# AFE.net
KiCad netlist of a schematic drawn in Altium Designer
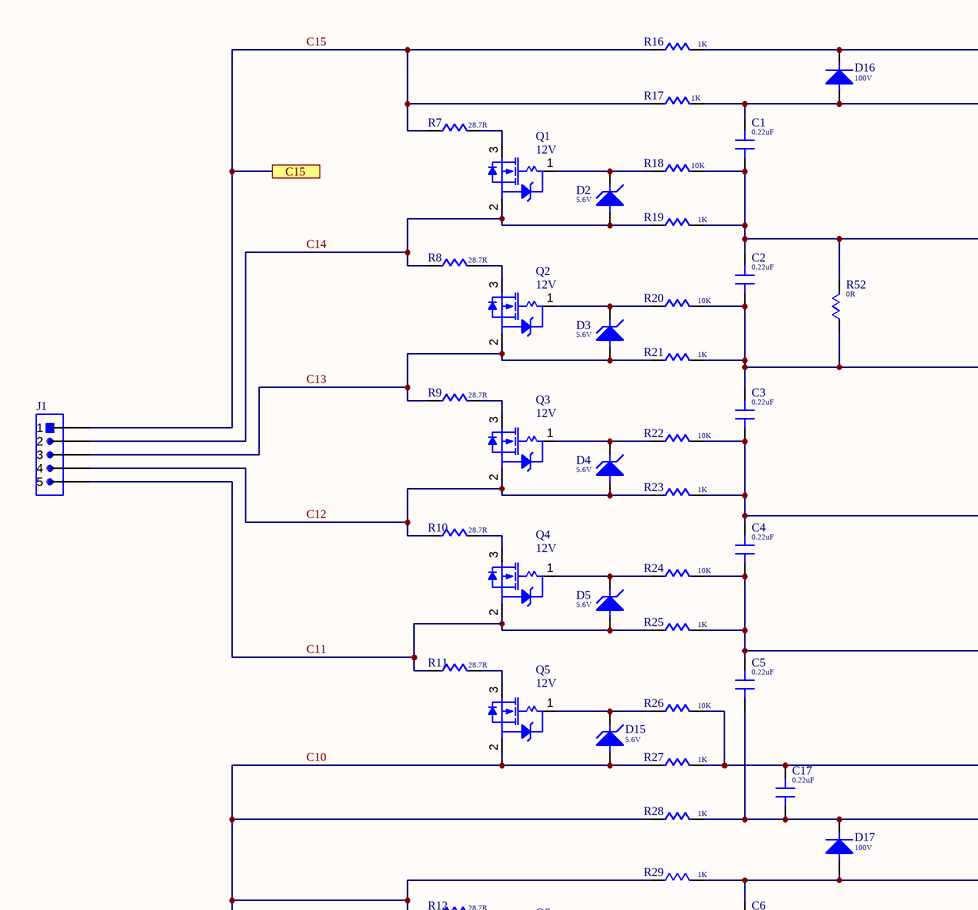
[diagram p0: AFE.SchDoc, top left]
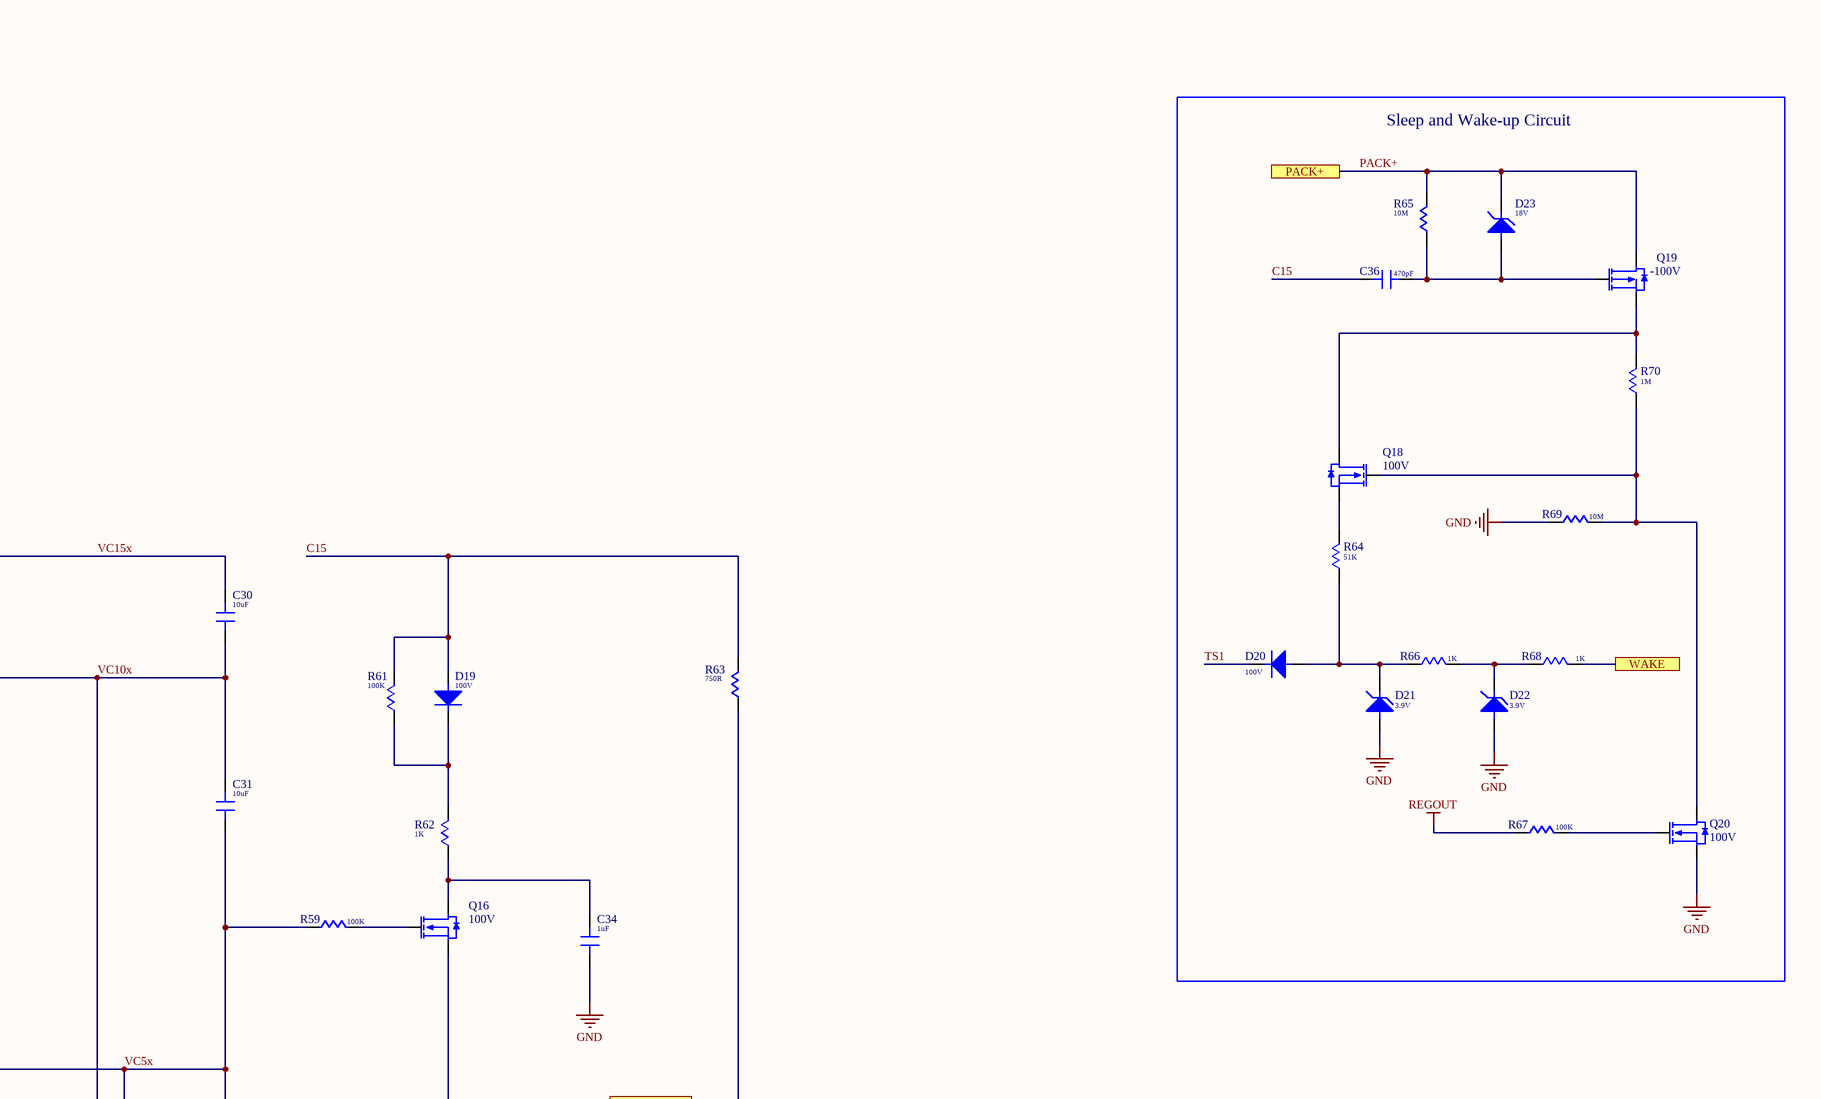
[diagram p1: AFE.SchDoc, top right]
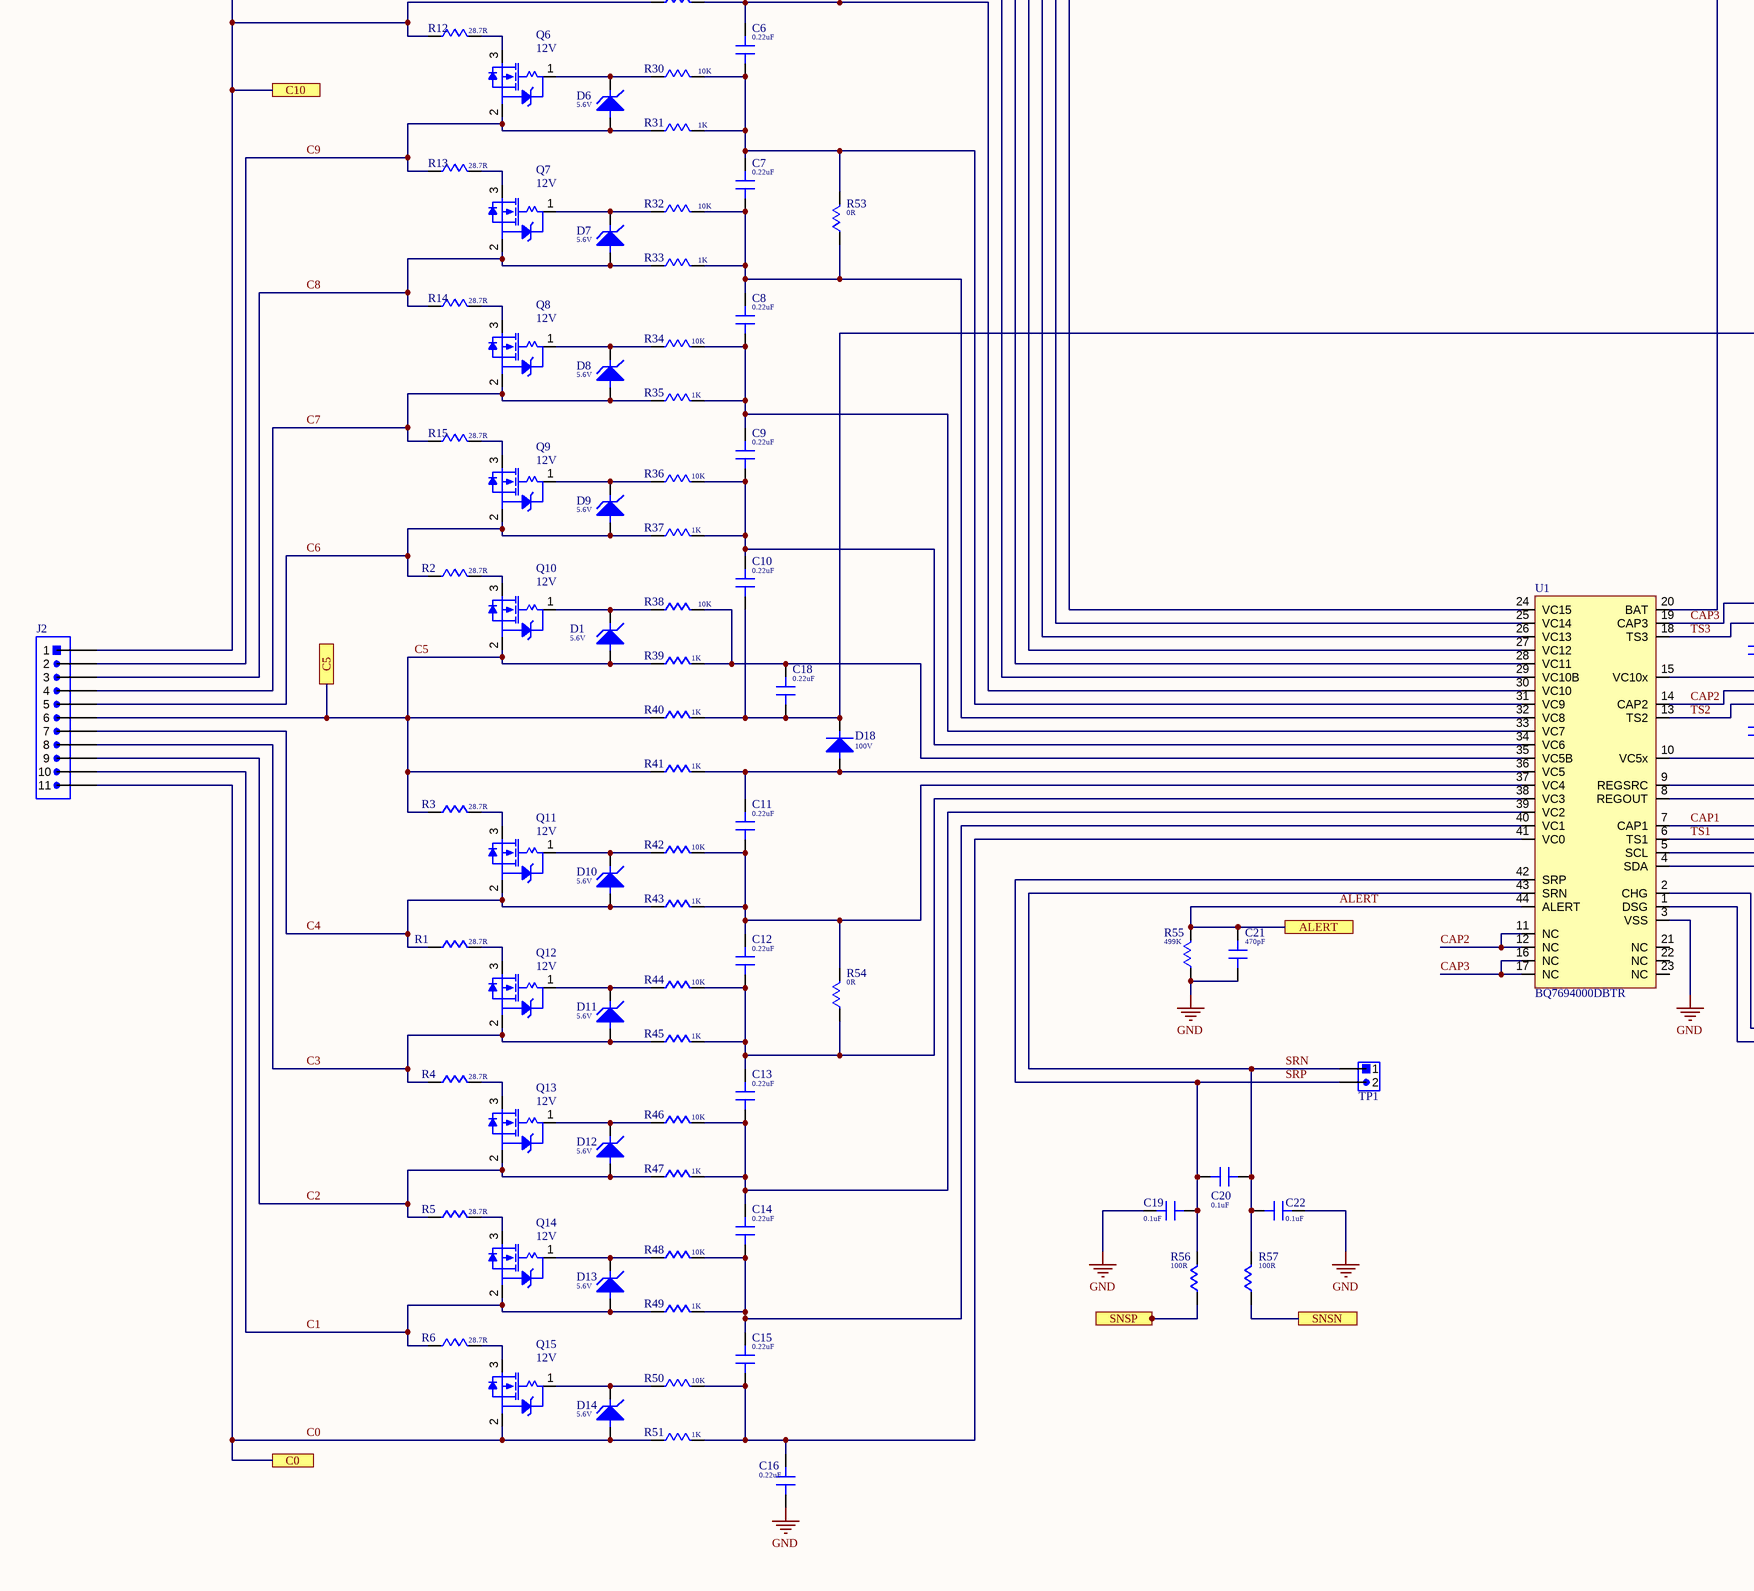
[diagram p2: AFE.SchDoc, bottom left]
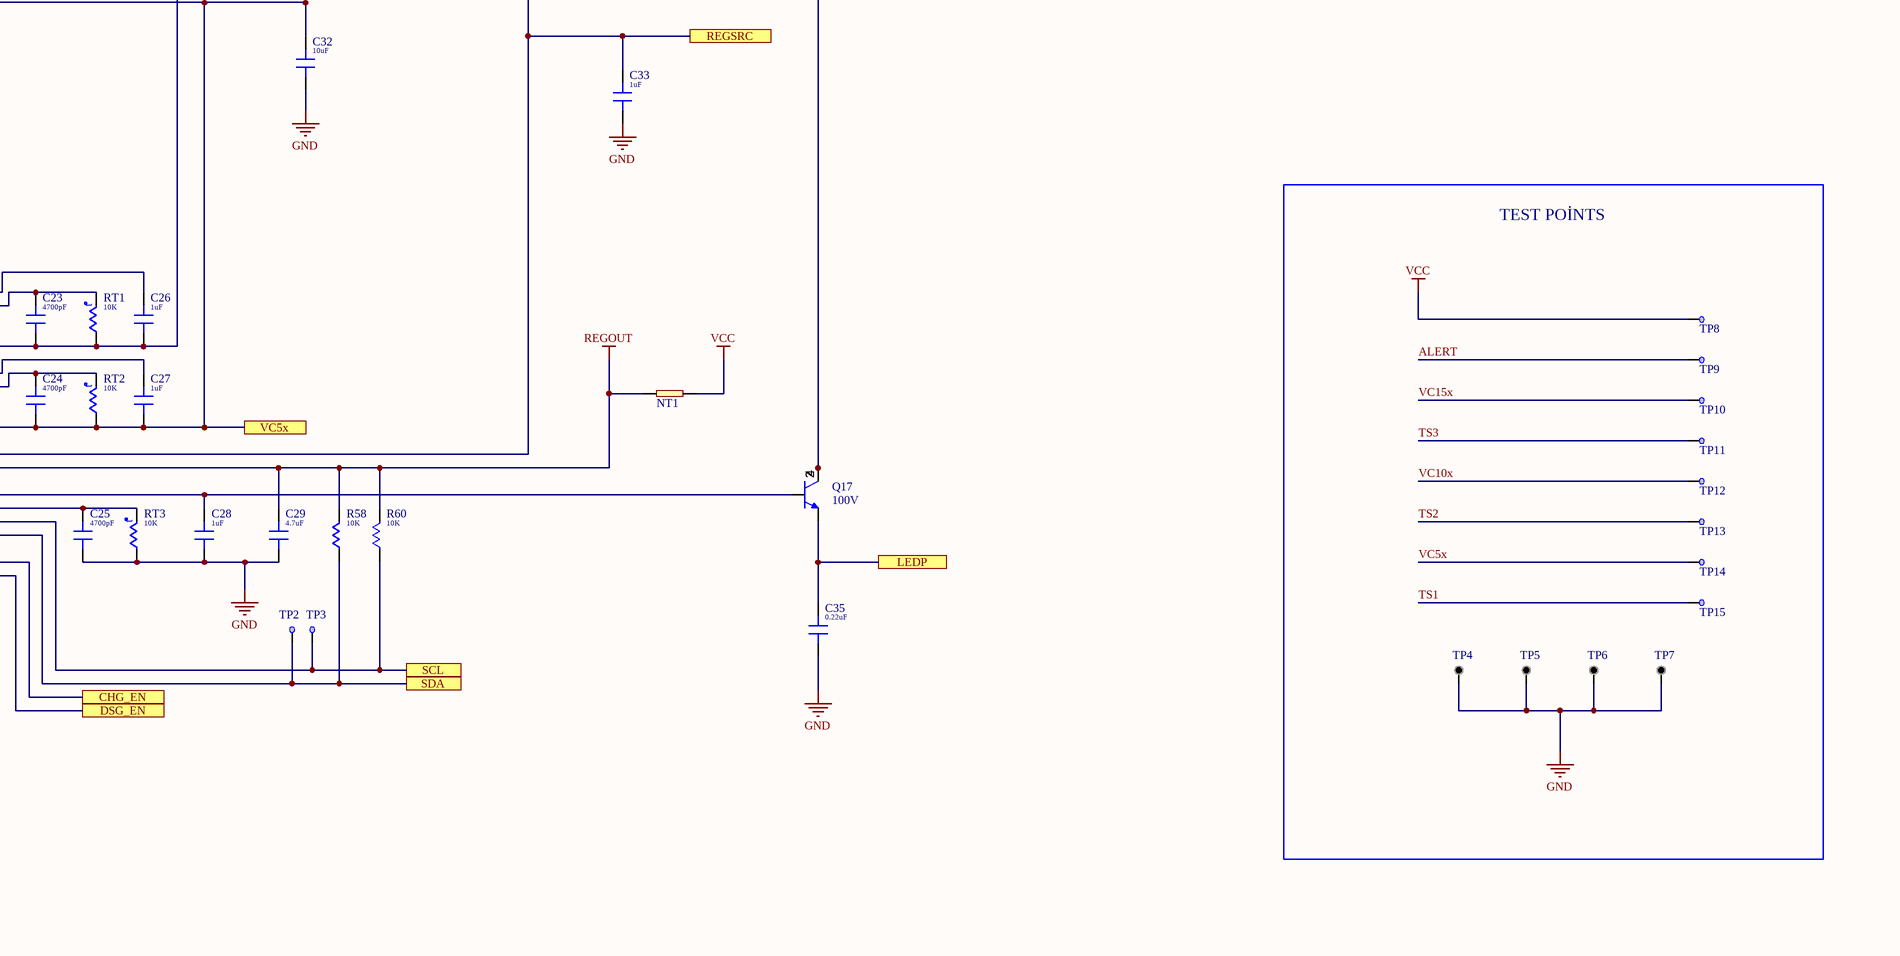
[diagram p3: AFE.SchDoc, bottom right]

(export (version "E")
  (design (tool "Eeschema 10.0.6"))
  (components
    (comp (ref "C1")
      (value "0.22uF")
      (footprint "C_0603")
      (description "Ceramic Capacitor 220nF, 16VDC, 0603, ±10 %")
      (fields
        (field (name "MANUFACTURER") "Wurth Electronics")
        (field (name "MANUFACTURER PART NUMBER") "885012206048")
      )
      (libsource (lib "BMS_Lib") (part "C_0.22uF_0603_16V"))
    )
    (comp (ref "C2")
      (value "0.22uF")
      (footprint "C_0603")
      (description "Ceramic Capacitor 220nF, 16VDC, 0603, ±10 %")
      (fields
        (field (name "MANUFACTURER") "Wurth Electronics")
        (field (name "MANUFACTURER PART NUMBER") "885012206048")
      )
      (libsource (lib "BMS_Lib") (part "C_0.22uF_0603_16V"))
    )
    (comp (ref "C3")
      (value "0.22uF")
      (footprint "C_0603")
      (description "Ceramic Capacitor 220nF, 16VDC, 0603, ±10 %")
      (fields
        (field (name "MANUFACTURER") "Wurth Electronics")
        (field (name "MANUFACTURER PART NUMBER") "885012206048")
      )
      (libsource (lib "BMS_Lib") (part "C_0.22uF_0603_16V"))
    )
    (comp (ref "C4")
      (value "0.22uF")
      (footprint "C_0603")
      (description "Ceramic Capacitor 220nF, 16VDC, 0603, ±10 %")
      (fields
        (field (name "MANUFACTURER") "Wurth Electronics")
        (field (name "MANUFACTURER PART NUMBER") "885012206048")
      )
      (libsource (lib "BMS_Lib") (part "C_0.22uF_0603_16V"))
    )
    (comp (ref "C5")
      (value "0.22uF")
      (footprint "C_0603")
      (description "Ceramic Capacitor 220nF, 16VDC, 0603, ±10 %")
      (fields
        (field (name "MANUFACTURER") "Wurth Electronics")
        (field (name "MANUFACTURER PART NUMBER") "885012206048")
      )
      (libsource (lib "BMS_Lib") (part "C_0.22uF_0603_16V"))
    )
    (comp (ref "C6")
      (value "0.22uF")
      (footprint "C_0603")
      (description "Ceramic Capacitor 220nF, 16VDC, 0603, ±10 %")
      (fields
        (field (name "MANUFACTURER") "Wurth Electronics")
        (field (name "MANUFACTURER PART NUMBER") "885012206048")
      )
      (libsource (lib "BMS_Lib") (part "C_0.22uF_0603_16V"))
    )
    (comp (ref "C7")
      (value "0.22uF")
      (footprint "C_0603")
      (description "Ceramic Capacitor 220nF, 16VDC, 0603, ±10 %")
      (fields
        (field (name "MANUFACTURER") "Wurth Electronics")
        (field (name "MANUFACTURER PART NUMBER") "885012206048")
      )
      (libsource (lib "BMS_Lib") (part "C_0.22uF_0603_16V"))
    )
    (comp (ref "C8")
      (value "0.22uF")
      (footprint "C_0603")
      (description "Ceramic Capacitor 220nF, 16VDC, 0603, ±10 %")
      (fields
        (field (name "MANUFACTURER") "Wurth Electronics")
        (field (name "MANUFACTURER PART NUMBER") "885012206048")
      )
      (libsource (lib "BMS_Lib") (part "C_0.22uF_0603_16V"))
    )
    (comp (ref "C9")
      (value "0.22uF")
      (footprint "C_0603")
      (description "Ceramic Capacitor 220nF, 16VDC, 0603, ±10 %")
      (fields
        (field (name "MANUFACTURER") "Wurth Electronics")
        (field (name "MANUFACTURER PART NUMBER") "885012206048")
      )
      (libsource (lib "BMS_Lib") (part "C_0.22uF_0603_16V"))
    )
    (comp (ref "C10")
      (value "0.22uF")
      (footprint "C_0603")
      (description "Ceramic Capacitor 220nF, 16VDC, 0603, ±10 %")
      (fields
        (field (name "MANUFACTURER") "Wurth Electronics")
        (field (name "MANUFACTURER PART NUMBER") "885012206048")
      )
      (libsource (lib "BMS_Lib") (part "C_0.22uF_0603_16V"))
    )
    (comp (ref "C11")
      (value "0.22uF")
      (footprint "C_0603")
      (description "Ceramic Capacitor 220nF, 16VDC, 0603, ±10 %")
      (fields
        (field (name "MANUFACTURER") "Wurth Electronics")
        (field (name "MANUFACTURER PART NUMBER") "885012206048")
      )
      (libsource (lib "BMS_Lib") (part "C_0.22uF_0603_16V"))
    )
    (comp (ref "C12")
      (value "0.22uF")
      (footprint "C_0603")
      (description "Ceramic Capacitor 220nF, 16VDC, 0603, ±10 %")
      (fields
        (field (name "MANUFACTURER") "Wurth Electronics")
        (field (name "MANUFACTURER PART NUMBER") "885012206048")
      )
      (libsource (lib "BMS_Lib") (part "C_0.22uF_0603_16V"))
    )
    (comp (ref "C13")
      (value "0.22uF")
      (footprint "C_0603")
      (description "Ceramic Capacitor 220nF, 16VDC, 0603, ±10 %")
      (fields
        (field (name "MANUFACTURER") "Wurth Electronics")
        (field (name "MANUFACTURER PART NUMBER") "885012206048")
      )
      (libsource (lib "BMS_Lib") (part "C_0.22uF_0603_16V"))
    )
    (comp (ref "C14")
      (value "0.22uF")
      (footprint "C_0603")
      (description "Ceramic Capacitor 220nF, 16VDC, 0603, ±10 %")
      (fields
        (field (name "MANUFACTURER") "Wurth Electronics")
        (field (name "MANUFACTURER PART NUMBER") "885012206048")
      )
      (libsource (lib "BMS_Lib") (part "C_0.22uF_0603_16V"))
    )
    (comp (ref "C15")
      (value "0.22uF")
      (footprint "C_0603")
      (description "Ceramic Capacitor 220nF, 16VDC, 0603, ±10 %")
      (fields
        (field (name "MANUFACTURER") "Wurth Electronics")
        (field (name "MANUFACTURER PART NUMBER") "885012206048")
      )
      (libsource (lib "BMS_Lib") (part "C_0.22uF_0603_16V"))
    )
    (comp (ref "C16")
      (value "0.22uF")
      (footprint "C_0603")
      (description "Ceramic Capacitor 220nF, 16VDC, 0603, ±10 %")
      (fields
        (field (name "MANUFACTURER") "Wurth Electronics")
        (field (name "MANUFACTURER PART NUMBER") "885012206048")
      )
      (libsource (lib "BMS_Lib") (part "C_0.22uF_0603_16V"))
    )
    (comp (ref "C17")
      (value "0.22uF")
      (footprint "C_0603")
      (description "Ceramic Capacitor 220nF, 16VDC, 0603, ±10 %")
      (fields
        (field (name "MANUFACTURER") "Wurth Electronics")
        (field (name "MANUFACTURER PART NUMBER") "885012206048")
      )
      (libsource (lib "BMS_Lib") (part "C_0.22uF_0603_16V"))
    )
    (comp (ref "C18")
      (value "0.22uF")
      (footprint "C_0603")
      (description "Ceramic Capacitor 220nF, 16VDC, 0603, ±10 %")
      (fields
        (field (name "MANUFACTURER") "Wurth Electronics")
        (field (name "MANUFACTURER PART NUMBER") "885012206048")
      )
      (libsource (lib "BMS_Lib") (part "C_0.22uF_0603_16V"))
    )
    (comp (ref "C19")
      (value "0.1uF")
      (footprint "C_0603")
      (description "Ceramic Capacitor, Multilayer, Ceramic, 50V, 10% -Tol, X7R, 15% Tc, 0.1Uf, Surface Mount, 0603")
      (fields
        (field (name "MANUFACTURER") "TDK")
        (field (name "MANUFACTURER PART NUMBER") "C1608X7R1H104K080AA")
      )
      (libsource (lib "BMS_Lib") (part "C_0.1uF_0603_50V"))
    )
    (comp (ref "C20")
      (value "0.1uF")
      (footprint "C_0603")
      (description "Ceramic Capacitor, Multilayer, Ceramic, 50V, 10% -Tol, X7R, 15% Tc, 0.1Uf, Surface Mount, 0603")
      (fields
        (field (name "MANUFACTURER") "TDK")
        (field (name "MANUFACTURER PART NUMBER") "C1608X7R1H104K080AA")
      )
      (libsource (lib "BMS_Lib") (part "C_0.1uF_0603_50V"))
    )
    (comp (ref "C21")
      (value "470pF")
      (footprint "C_0603")
      (description "WCAP-CSGP 0603 (1608Metric) Ceramic Capacitor 0.063Lx0.031W 1.60mmx0.80mm X7R ±10% 470pF")
      (fields
        (field (name "MANUFACTURER") "Wurth Electronics")
        (field (name "MANUFACTURER PART NUMBER") "885012206081")
      )
      (libsource (lib "BMS_Lib") (part "C_470pF_0603_50V"))
    )
    (comp (ref "C22")
      (value "0.1uF")
      (footprint "C_0603")
      (description "Ceramic Capacitor, Multilayer, Ceramic, 50V, 10% -Tol, X7R, 15% Tc, 0.1Uf, Surface Mount, 0603")
      (fields
        (field (name "MANUFACTURER") "TDK")
        (field (name "MANUFACTURER PART NUMBER") "C1608X7R1H104K080AA")
      )
      (libsource (lib "BMS_Lib") (part "C_0.1uF_0603_50V"))
    )
    (comp (ref "C23")
      (value "4700pF")
      (footprint "C_0603")
      (description "Cap Cer 4700PF 50V X7R 0603")
      (fields
        (field (name "MANUFACTURER") "Wurth Electronics")
        (field (name "MANUFACTURER PART NUMBER") "885012206087")
      )
      (libsource (lib "BMS_Lib") (part "C_4700pF_0603_50V"))
    )
    (comp (ref "C24")
      (value "4700pF")
      (footprint "C_0603")
      (description "Cap Cer 4700PF 50V X7R 0603")
      (fields
        (field (name "MANUFACTURER") "Wurth Electronics")
        (field (name "MANUFACTURER PART NUMBER") "885012206087")
      )
      (libsource (lib "BMS_Lib") (part "C_4700pF_0603_50V"))
    )
    (comp (ref "C25")
      (value "4700pF")
      (footprint "C_0603")
      (description "Cap Cer 4700PF 50V X7R 0603")
      (fields
        (field (name "MANUFACTURER") "Wurth Electronics")
        (field (name "MANUFACTURER PART NUMBER") "885012206087")
      )
      (libsource (lib "BMS_Lib") (part "C_4700pF_0603_50V"))
    )
    (comp (ref "C26")
      (value "1uF")
      (footprint "C_0603")
      (fields
        (field (name "MANUFACTURER") "Wurth Electronics")
        (field (name "MANUFACTURER PART NUMBER") "885012206052")
        (field (name "TOLERANCE") "10%")
      )
      (libsource (lib "BMS_Lib") (part "C_1uF_0603_16V"))
    )
    (comp (ref "C27")
      (value "1uF")
      (footprint "C_0603")
      (fields
        (field (name "MANUFACTURER") "Wurth Electronics")
        (field (name "MANUFACTURER PART NUMBER") "885012206052")
        (field (name "TOLERANCE") "10%")
      )
      (libsource (lib "BMS_Lib") (part "C_1uF_0603_16V"))
    )
    (comp (ref "C28")
      (value "1uF")
      (footprint "C_0603")
      (fields
        (field (name "MANUFACTURER") "Wurth Electronics")
        (field (name "MANUFACTURER PART NUMBER") "885012206052")
        (field (name "TOLERANCE") "10%")
      )
      (libsource (lib "BMS_Lib") (part "C_1uF_0603_16V"))
    )
    (comp (ref "C29")
      (value "4.7uF")
      (footprint "C_0805")
      (fields
        (field (name "MANUFACTURER") "Wurth Electronics")
        (field (name "MANUFACTURER PART NUMBER") "885012207025")
      )
      (libsource (lib "BMS_Lib") (part "C_4.7uF_0805_10V"))
    )
    (comp (ref "C30")
      (value "10uF")
      (footprint "C_1210")
      (description "Multilayer Ceramic Capacitor, 10 uF, 35 V, ± 10%, X7R, 1210 [3225 Metric]")
      (fields
        (field (name "MANUFACTURER") "Murata")
        (field (name "MANUFACTURER PART NUMBER") "GRM32ER7YA106KA12L")
      )
      (libsource (lib "BMS_Lib") (part "C_10uF_1210_35V"))
    )
    (comp (ref "C31")
      (value "10uF")
      (footprint "C_1210")
      (description "Multilayer Ceramic Capacitor, 10 uF, 35 V, ± 10%, X7R, 1210 [3225 Metric]")
      (fields
        (field (name "MANUFACTURER") "Murata")
        (field (name "MANUFACTURER PART NUMBER") "GRM32ER7YA106KA12L")
      )
      (libsource (lib "BMS_Lib") (part "C_10uF_1210_35V"))
    )
    (comp (ref "C32")
      (value "10uF")
      (footprint "C_1210")
      (description "Multilayer Ceramic Capacitor, 10 uF, 35 V, ± 10%, X7R, 1210 [3225 Metric]")
      (fields
        (field (name "MANUFACTURER") "Murata")
        (field (name "MANUFACTURER PART NUMBER") "GRM32ER7YA106KA12L")
      )
      (libsource (lib "BMS_Lib") (part "C_10uF_1210_35V"))
    )
    (comp (ref "C33")
      (value "1uF")
      (footprint "C_0805")
      (description "CAP CER 1UF 50V X7R 0805")
      (fields (field (name "TOLERANCE") "+-10%") (field (name "Comment") "GRM21BR71H105KA12L"))
      (libsource (lib "BMS_Lib") (part "C_1uF_0805_50V"))
    )
    (comp (ref "C34")
      (value "1uF")
      (footprint "C_0805")
      (description "CAP CER 1UF 50V X7R 0805")
      (fields (field (name "TOLERANCE") "+-10%") (field (name "Comment") "GRM21BR71H105KA12L"))
      (libsource (lib "BMS_Lib") (part "C_1uF_0805_50V"))
    )
    (comp (ref "C35")
      (value "0.22uF")
      (footprint "C_0603")
      (description "Ceramic Capacitor 220nF, 16VDC, 0603, ±10 %")
      (fields
        (field (name "MANUFACTURER") "Wurth Electronics")
        (field (name "MANUFACTURER PART NUMBER") "885012206048")
      )
      (libsource (lib "BMS_Lib") (part "C_0.22uF_0603_16V"))
    )
    (comp (ref "C36")
      (value "470pF")
      (footprint "C_0603")
      (description "WCAP-CSGP 0603 (1608Metric) Ceramic Capacitor 0.063Lx0.031W 1.60mmx0.80mm X7R ±10% 470pF")
      (fields
        (field (name "MANUFACTURER") "Wurth Electronics")
        (field (name "MANUFACTURER PART NUMBER") "885012206081")
      )
      (libsource (lib "BMS_Lib") (part "C_470pF_0603_50V"))
    )
    (comp (ref "D1")
      (value "5.6V")
      (footprint "D_SOD323")
      (description "Diode Zener Single 5.6V 5% 200mW Automotive 2-Pin SOD-323 T/R")
      (fields
        (field (name "MANUFACTURER") "Diodes")
        (field (name "MANUFACTURER PART NUMBER") "MMSZ5232BS-7-F")
      )
      (libsource (lib "BMS_Lib") (part "D_ZENER_5.6V_SOD323"))
    )
    (comp (ref "D2")
      (value "5.6V")
      (footprint "D_SOD323")
      (description "Diode Zener Single 5.6V 5% 200mW Automotive 2-Pin SOD-323 T/R")
      (fields
        (field (name "MANUFACTURER") "Diodes")
        (field (name "MANUFACTURER PART NUMBER") "MMSZ5232BS-7-F")
      )
      (libsource (lib "BMS_Lib") (part "D_ZENER_5.6V_SOD323"))
    )
    (comp (ref "D3")
      (value "5.6V")
      (footprint "D_SOD323")
      (description "Diode Zener Single 5.6V 5% 200mW Automotive 2-Pin SOD-323 T/R")
      (fields
        (field (name "MANUFACTURER") "Diodes")
        (field (name "MANUFACTURER PART NUMBER") "MMSZ5232BS-7-F")
      )
      (libsource (lib "BMS_Lib") (part "D_ZENER_5.6V_SOD323"))
    )
    (comp (ref "D4")
      (value "5.6V")
      (footprint "D_SOD323")
      (description "Diode Zener Single 5.6V 5% 200mW Automotive 2-Pin SOD-323 T/R")
      (fields
        (field (name "MANUFACTURER") "Diodes")
        (field (name "MANUFACTURER PART NUMBER") "MMSZ5232BS-7-F")
      )
      (libsource (lib "BMS_Lib") (part "D_ZENER_5.6V_SOD323"))
    )
    (comp (ref "D5")
      (value "5.6V")
      (footprint "D_SOD323")
      (description "Diode Zener Single 5.6V 5% 200mW Automotive 2-Pin SOD-323 T/R")
      (fields
        (field (name "MANUFACTURER") "Diodes")
        (field (name "MANUFACTURER PART NUMBER") "MMSZ5232BS-7-F")
      )
      (libsource (lib "BMS_Lib") (part "D_ZENER_5.6V_SOD323"))
    )
    (comp (ref "D6")
      (value "5.6V")
      (footprint "D_SOD323")
      (description "Diode Zener Single 5.6V 5% 200mW Automotive 2-Pin SOD-323 T/R")
      (fields
        (field (name "MANUFACTURER") "Diodes")
        (field (name "MANUFACTURER PART NUMBER") "MMSZ5232BS-7-F")
      )
      (libsource (lib "BMS_Lib") (part "D_ZENER_5.6V_SOD323"))
    )
    (comp (ref "D7")
      (value "5.6V")
      (footprint "D_SOD323")
      (description "Diode Zener Single 5.6V 5% 200mW Automotive 2-Pin SOD-323 T/R")
      (fields
        (field (name "MANUFACTURER") "Diodes")
        (field (name "MANUFACTURER PART NUMBER") "MMSZ5232BS-7-F")
      )
      (libsource (lib "BMS_Lib") (part "D_ZENER_5.6V_SOD323"))
    )
    (comp (ref "D8")
      (value "5.6V")
      (footprint "D_SOD323")
      (description "Diode Zener Single 5.6V 5% 200mW Automotive 2-Pin SOD-323 T/R")
      (fields
        (field (name "MANUFACTURER") "Diodes")
        (field (name "MANUFACTURER PART NUMBER") "MMSZ5232BS-7-F")
      )
      (libsource (lib "BMS_Lib") (part "D_ZENER_5.6V_SOD323"))
    )
    (comp (ref "D9")
      (value "5.6V")
      (footprint "D_SOD323")
      (description "Diode Zener Single 5.6V 5% 200mW Automotive 2-Pin SOD-323 T/R")
      (fields
        (field (name "MANUFACTURER") "Diodes")
        (field (name "MANUFACTURER PART NUMBER") "MMSZ5232BS-7-F")
      )
      (libsource (lib "BMS_Lib") (part "D_ZENER_5.6V_SOD323"))
    )
    (comp (ref "D10")
      (value "5.6V")
      (footprint "D_SOD323")
      (description "Diode Zener Single 5.6V 5% 200mW Automotive 2-Pin SOD-323 T/R")
      (fields
        (field (name "MANUFACTURER") "Diodes")
        (field (name "MANUFACTURER PART NUMBER") "MMSZ5232BS-7-F")
      )
      (libsource (lib "BMS_Lib") (part "D_ZENER_5.6V_SOD323"))
    )
    (comp (ref "D11")
      (value "5.6V")
      (footprint "D_SOD323")
      (description "Diode Zener Single 5.6V 5% 200mW Automotive 2-Pin SOD-323 T/R")
      (fields
        (field (name "MANUFACTURER") "Diodes")
        (field (name "MANUFACTURER PART NUMBER") "MMSZ5232BS-7-F")
      )
      (libsource (lib "BMS_Lib") (part "D_ZENER_5.6V_SOD323"))
    )
    (comp (ref "D12")
      (value "5.6V")
      (footprint "D_SOD323")
      (description "Diode Zener Single 5.6V 5% 200mW Automotive 2-Pin SOD-323 T/R")
      (fields
        (field (name "MANUFACTURER") "Diodes")
        (field (name "MANUFACTURER PART NUMBER") "MMSZ5232BS-7-F")
      )
      (libsource (lib "BMS_Lib") (part "D_ZENER_5.6V_SOD323"))
    )
    (comp (ref "D13")
      (value "5.6V")
      (footprint "D_SOD323")
      (description "Diode Zener Single 5.6V 5% 200mW Automotive 2-Pin SOD-323 T/R")
      (fields
        (field (name "MANUFACTURER") "Diodes")
        (field (name "MANUFACTURER PART NUMBER") "MMSZ5232BS-7-F")
      )
      (libsource (lib "BMS_Lib") (part "D_ZENER_5.6V_SOD323"))
    )
    (comp (ref "D14")
      (value "5.6V")
      (footprint "D_SOD323")
      (description "Diode Zener Single 5.6V 5% 200mW Automotive 2-Pin SOD-323 T/R")
      (fields
        (field (name "MANUFACTURER") "Diodes")
        (field (name "MANUFACTURER PART NUMBER") "MMSZ5232BS-7-F")
      )
      (libsource (lib "BMS_Lib") (part "D_ZENER_5.6V_SOD323"))
    )
    (comp (ref "D15")
      (value "5.6V")
      (footprint "D_SOD323")
      (description "Diode Zener Single 5.6V 5% 200mW Automotive 2-Pin SOD-323 T/R")
      (fields
        (field (name "MANUFACTURER") "Diodes")
        (field (name "MANUFACTURER PART NUMBER") "MMSZ5232BS-7-F")
      )
      (libsource (lib "BMS_Lib") (part "D_ZENER_5.6V_SOD323"))
    )
    (comp (ref "D16")
      (value "100V")
      (footprint "D_SOD123")
      (description "Small Signal Diode, Single, 100 V, 300 mA, 1.25 V, 4 ns, 2 A RoHS Compliant: Yes")
      (fields (field (name "MANUFACTURER") "Diodes") (field (name "MANUFACTURER PART NUMBER") "1N4148W-7-F"))
      (libsource (lib "BMS_Lib") (part "D_GENPURP_100V_SOD123"))
    )
    (comp (ref "D17")
      (value "100V")
      (footprint "D_SOD123")
      (description "Small Signal Diode, Single, 100 V, 300 mA, 1.25 V, 4 ns, 2 A RoHS Compliant: Yes")
      (fields (field (name "MANUFACTURER") "Diodes") (field (name "MANUFACTURER PART NUMBER") "1N4148W-7-F"))
      (libsource (lib "BMS_Lib") (part "D_GENPURP_100V_SOD123"))
    )
    (comp (ref "D18")
      (value "100V")
      (footprint "D_SOD123")
      (description "Small Signal Diode, Single, 100 V, 300 mA, 1.25 V, 4 ns, 2 A RoHS Compliant: Yes")
      (fields (field (name "MANUFACTURER") "Diodes") (field (name "MANUFACTURER PART NUMBER") "1N4148W-7-F"))
      (libsource (lib "BMS_Lib") (part "D_GENPURP_100V_SOD123"))
    )
    (comp (ref "D19")
      (value "100V")
      (footprint "D_SOD123")
      (description "Small Signal Diode, Single, 100 V, 300 mA, 1.25 V, 4 ns, 2 A RoHS Compliant: Yes")
      (fields (field (name "MANUFACTURER") "Diodes") (field (name "MANUFACTURER PART NUMBER") "1N4148W-7-F"))
      (libsource (lib "BMS_Lib") (part "D_GENPURP_100V_SOD123"))
    )
    (comp (ref "D20")
      (value "100V")
      (footprint "D_SOD123")
      (description "Small Signal Diode, Single, 100 V, 300 mA, 1.25 V, 4 ns, 2 A RoHS Compliant: Yes")
      (fields (field (name "MANUFACTURER") "Diodes") (field (name "MANUFACTURER PART NUMBER") "1N4148W-7-F"))
      (libsource (lib "BMS_Lib") (part "D_GENPURP_100V_SOD123"))
    )
    (comp (ref "D21")
      (value "3.9V")
      (footprint "D_SOD323")
      (description "MMSZ5228BS Series 3.9 V 10 mA 200 mW Surface Mount Zener Diode - SOD-323")
      (fields
        (field (name "MANUFACTURER") "Diodes")
        (field (name "MANUFACTURER PART NUMBER") "MMSZ5228BS-7-F")
      )
      (libsource (lib "BMS_Lib") (part "D_ZENER_3.9V_SOD323"))
    )
    (comp (ref "D22")
      (value "3.9V")
      (footprint "D_SOD323")
      (description "MMSZ5228BS Series 3.9 V 10 mA 200 mW Surface Mount Zener Diode - SOD-323")
      (fields
        (field (name "MANUFACTURER") "Diodes")
        (field (name "MANUFACTURER PART NUMBER") "MMSZ5228BS-7-F")
      )
      (libsource (lib "BMS_Lib") (part "D_ZENER_3.9V_SOD323"))
    )
    (comp (ref "D23")
      (value "18V")
      (footprint "D_SOD323")
      (description "Diode Zener Single 18V 5% 200mW Automotive 2-Pin SOD-323 T/R")
      (fields
        (field (name "MANUFACTURER") "Diodes")
        (field (name "MANUFACTURER PART NUMBER") "MMSZ5248BS-7-F")
      )
      (libsource (lib "BMS_Lib") (part "D_ZENER_18V_SOD323"))
    )
    (comp (ref "J1")
      (value "0395021005")
      (footprint "TB_5")
      (description "Conn Shrouded Header (4 Sides) HDR 5 POS 3.5mm Solder RA Side Entry Thru-Hole Eurostyle™")
      (fields (field (name "MANUFACTURER") "Molex") (field (name "VOLTAGE") "300V"))
      (libsource (lib "BMS_Lib") (part "J_TERMBLOCK_5POS_3.5MM"))
    )
    (comp (ref "J2")
      (value "0395021011")
      (footprint "TB_11")
      (description "Conn Shrouded Header (4 Sides) HDR 11 POS 3.5mm Solder RA Thru-Hole Eurostyle™")
      (fields (field (name "MANUFACTURER") "Molex") (field (name "VOLTAGE") "300V"))
      (libsource (lib "BMS_Lib") (part "J_TERMBLOCK_11POS_3.5MM"))
    )
    (comp (ref "NT1")
      (value "Net Tie")
      (footprint "NET_TİE_1")
      (description "Single point connection between nets.")
      (libsource (lib "BMS_Lib") (part "NET_TİE_1"))
    )
    (comp (ref "Q1")
      (value "CSD13381F4")
      (footprint "Q_3PICOSTAR")
      (description "MOSFET N-CH 12V 2.1A 3PICOSTAR / Trans MOSFET N-CH 12V 2.1A 3-Pin PicoStar T/R")
      (fields (field (name "MANUFACTURER") "Texas Instruments") (field (name "VOLTAGE") "12V"))
      (libsource (lib "BMS_Lib") (part "Q_MOSFET_12V_PICOSTAR3"))
    )
    (comp (ref "Q2")
      (value "CSD13381F4")
      (footprint "Q_3PICOSTAR")
      (description "MOSFET N-CH 12V 2.1A 3PICOSTAR / Trans MOSFET N-CH 12V 2.1A 3-Pin PicoStar T/R")
      (fields (field (name "MANUFACTURER") "Texas Instruments") (field (name "VOLTAGE") "12V"))
      (libsource (lib "BMS_Lib") (part "Q_MOSFET_12V_PICOSTAR3"))
    )
    (comp (ref "Q3")
      (value "CSD13381F4")
      (footprint "Q_3PICOSTAR")
      (description "MOSFET N-CH 12V 2.1A 3PICOSTAR / Trans MOSFET N-CH 12V 2.1A 3-Pin PicoStar T/R")
      (fields (field (name "MANUFACTURER") "Texas Instruments") (field (name "VOLTAGE") "12V"))
      (libsource (lib "BMS_Lib") (part "Q_MOSFET_12V_PICOSTAR3"))
    )
    (comp (ref "Q4")
      (value "CSD13381F4")
      (footprint "Q_3PICOSTAR")
      (description "MOSFET N-CH 12V 2.1A 3PICOSTAR / Trans MOSFET N-CH 12V 2.1A 3-Pin PicoStar T/R")
      (fields (field (name "MANUFACTURER") "Texas Instruments") (field (name "VOLTAGE") "12V"))
      (libsource (lib "BMS_Lib") (part "Q_MOSFET_12V_PICOSTAR3"))
    )
    (comp (ref "Q5")
      (value "CSD13381F4")
      (footprint "Q_3PICOSTAR")
      (description "MOSFET N-CH 12V 2.1A 3PICOSTAR / Trans MOSFET N-CH 12V 2.1A 3-Pin PicoStar T/R")
      (fields (field (name "MANUFACTURER") "Texas Instruments") (field (name "VOLTAGE") "12V"))
      (libsource (lib "BMS_Lib") (part "Q_MOSFET_12V_PICOSTAR3"))
    )
    (comp (ref "Q6")
      (value "CSD13381F4")
      (footprint "Q_3PICOSTAR")
      (description "MOSFET N-CH 12V 2.1A 3PICOSTAR / Trans MOSFET N-CH 12V 2.1A 3-Pin PicoStar T/R")
      (fields (field (name "MANUFACTURER") "Texas Instruments") (field (name "VOLTAGE") "12V"))
      (libsource (lib "BMS_Lib") (part "Q_MOSFET_12V_PICOSTAR3"))
    )
    (comp (ref "Q7")
      (value "CSD13381F4")
      (footprint "Q_3PICOSTAR")
      (description "MOSFET N-CH 12V 2.1A 3PICOSTAR / Trans MOSFET N-CH 12V 2.1A 3-Pin PicoStar T/R")
      (fields (field (name "MANUFACTURER") "Texas Instruments") (field (name "VOLTAGE") "12V"))
      (libsource (lib "BMS_Lib") (part "Q_MOSFET_12V_PICOSTAR3"))
    )
    (comp (ref "Q8")
      (value "CSD13381F4")
      (footprint "Q_3PICOSTAR")
      (description "MOSFET N-CH 12V 2.1A 3PICOSTAR / Trans MOSFET N-CH 12V 2.1A 3-Pin PicoStar T/R")
      (fields (field (name "MANUFACTURER") "Texas Instruments") (field (name "VOLTAGE") "12V"))
      (libsource (lib "BMS_Lib") (part "Q_MOSFET_12V_PICOSTAR3"))
    )
    (comp (ref "Q9")
      (value "CSD13381F4")
      (footprint "Q_3PICOSTAR")
      (description "MOSFET N-CH 12V 2.1A 3PICOSTAR / Trans MOSFET N-CH 12V 2.1A 3-Pin PicoStar T/R")
      (fields (field (name "MANUFACTURER") "Texas Instruments") (field (name "VOLTAGE") "12V"))
      (libsource (lib "BMS_Lib") (part "Q_MOSFET_12V_PICOSTAR3"))
    )
    (comp (ref "Q10")
      (value "CSD13381F4")
      (footprint "Q_3PICOSTAR")
      (description "MOSFET N-CH 12V 2.1A 3PICOSTAR / Trans MOSFET N-CH 12V 2.1A 3-Pin PicoStar T/R")
      (fields (field (name "MANUFACTURER") "Texas Instruments") (field (name "VOLTAGE") "12V"))
      (libsource (lib "BMS_Lib") (part "Q_MOSFET_12V_PICOSTAR3"))
    )
    (comp (ref "Q11")
      (value "CSD13381F4")
      (footprint "Q_3PICOSTAR")
      (description "MOSFET N-CH 12V 2.1A 3PICOSTAR / Trans MOSFET N-CH 12V 2.1A 3-Pin PicoStar T/R")
      (fields (field (name "MANUFACTURER") "Texas Instruments") (field (name "VOLTAGE") "12V"))
      (libsource (lib "BMS_Lib") (part "Q_MOSFET_12V_PICOSTAR3"))
    )
    (comp (ref "Q12")
      (value "CSD13381F4")
      (footprint "Q_3PICOSTAR")
      (description "MOSFET N-CH 12V 2.1A 3PICOSTAR / Trans MOSFET N-CH 12V 2.1A 3-Pin PicoStar T/R")
      (fields (field (name "MANUFACTURER") "Texas Instruments") (field (name "VOLTAGE") "12V"))
      (libsource (lib "BMS_Lib") (part "Q_MOSFET_12V_PICOSTAR3"))
    )
    (comp (ref "Q13")
      (value "CSD13381F4")
      (footprint "Q_3PICOSTAR")
      (description "MOSFET N-CH 12V 2.1A 3PICOSTAR / Trans MOSFET N-CH 12V 2.1A 3-Pin PicoStar T/R")
      (fields (field (name "MANUFACTURER") "Texas Instruments") (field (name "VOLTAGE") "12V"))
      (libsource (lib "BMS_Lib") (part "Q_MOSFET_12V_PICOSTAR3"))
    )
    (comp (ref "Q14")
      (value "CSD13381F4")
      (footprint "Q_3PICOSTAR")
      (description "MOSFET N-CH 12V 2.1A 3PICOSTAR / Trans MOSFET N-CH 12V 2.1A 3-Pin PicoStar T/R")
      (fields (field (name "MANUFACTURER") "Texas Instruments") (field (name "VOLTAGE") "12V"))
      (libsource (lib "BMS_Lib") (part "Q_MOSFET_12V_PICOSTAR3"))
    )
    (comp (ref "Q15")
      (value "CSD13381F4")
      (footprint "Q_3PICOSTAR")
      (description "MOSFET N-CH 12V 2.1A 3PICOSTAR / Trans MOSFET N-CH 12V 2.1A 3-Pin PicoStar T/R")
      (fields (field (name "MANUFACTURER") "Texas Instruments") (field (name "VOLTAGE") "12V"))
      (libsource (lib "BMS_Lib") (part "Q_MOSFET_12V_PICOSTAR3"))
    )
    (comp (ref "Q16")
      (value "BST82,215")
      (footprint "Q_SOT23-3")
      (description "MOSFET N-CH 100V 190MA SOT-23")
      (fields (field (name "MANUFACTURER") "Nexperia") (field (name "VOLTAGE") "100V"))
      (libsource (lib "BMS_Lib") (part "Q_MOSFET_100V_SOT23"))
    )
    (comp (ref "Q17")
      (value "ZXTN19100CZTA")
      (footprint "Q_SOT-89-3")
      (description "TRANS NPN 100V 5.25A SOT89")
      (fields (field (name "MANUFACTURER") "Diodes Zetex") (field (name "VOLTAGE") "100V"))
      (libsource (lib "BMS_Lib") (part "Q_BJT_100V_SOT-89-3"))
    )
    (comp (ref "Q18")
      (value "BSS123")
      (footprint "Q_SOT23-3")
      (description "Transistor MOSFET Negative Channel 100 Volt 0.17A 3-Pin SOT-23")
      (fields (field (name "MANUFACTURER") "ON Semiconductor / Fairchild") (field (name "VOLTAGE") "100V"))
      (libsource (lib "BMS_Lib") (part "Q_MOSFET_100V_SOT23-3"))
    )
    (comp (ref "Q19")
      (value "ZXMP10A13FTA")
      (footprint "Q_SOT23-3")
      (description "P-Channel 100 V 1 Ohm Surface Mount Enhancement Mode MOSFET - SOT-23")
      (fields (field (name "MANUFACTURER") "Diodes Zetex") (field (name "VOLTAGE RATING (DC)") "-100V"))
      (libsource (lib "BMS_Lib") (part "Q_MOSFET_100V_SOT23-3_1"))
    )
    (comp (ref "Q20")
      (value "BSS123")
      (footprint "Q_SOT23-3")
      (description "Transistor MOSFET Negative Channel 100 Volt 0.17A 3-Pin SOT-23")
      (fields (field (name "MANUFACTURER") "ON Semiconductor / Fairchild") (field (name "VOLTAGE") "100V"))
      (libsource (lib "BMS_Lib") (part "Q_MOSFET_100V_SOT23-3"))
    )
    (comp (ref "R1")
      (value "28.7R")
      (footprint "R_2010")
      (description "SMD Chip Resistor, 28.7 Ohm, ± 1%, 750 mW, 2010 [5025 Metric], Thick Film, General Purpose")
      (fields
        (field (name "MANUFACTURER") "Vishay Dale")
        (field (name "MANUFACTURER PART NUMBER") "CRCW201028R7FKEF")
      )
      (libsource (lib "BMS_Lib") (part "R_28.7OHM_%1_3/4W_2010"))
    )
    (comp (ref "R2")
      (value "28.7R")
      (footprint "R_2010")
      (description "SMD Chip Resistor, 28.7 Ohm, ± 1%, 750 mW, 2010 [5025 Metric], Thick Film, General Purpose")
      (fields
        (field (name "MANUFACTURER") "Vishay Dale")
        (field (name "MANUFACTURER PART NUMBER") "CRCW201028R7FKEF")
      )
      (libsource (lib "BMS_Lib") (part "R_28.7OHM_%1_3/4W_2010"))
    )
    (comp (ref "R3")
      (value "28.7R")
      (footprint "R_2010")
      (description "SMD Chip Resistor, 28.7 Ohm, ± 1%, 750 mW, 2010 [5025 Metric], Thick Film, General Purpose")
      (fields
        (field (name "MANUFACTURER") "Vishay Dale")
        (field (name "MANUFACTURER PART NUMBER") "CRCW201028R7FKEF")
      )
      (libsource (lib "BMS_Lib") (part "R_28.7OHM_%1_3/4W_2010"))
    )
    (comp (ref "R4")
      (value "28.7R")
      (footprint "R_2010")
      (description "SMD Chip Resistor, 28.7 Ohm, ± 1%, 750 mW, 2010 [5025 Metric], Thick Film, General Purpose")
      (fields
        (field (name "MANUFACTURER") "Vishay Dale")
        (field (name "MANUFACTURER PART NUMBER") "CRCW201028R7FKEF")
      )
      (libsource (lib "BMS_Lib") (part "R_28.7OHM_%1_3/4W_2010"))
    )
    (comp (ref "R5")
      (value "28.7R")
      (footprint "R_2010")
      (description "SMD Chip Resistor, 28.7 Ohm, ± 1%, 750 mW, 2010 [5025 Metric], Thick Film, General Purpose")
      (fields
        (field (name "MANUFACTURER") "Vishay Dale")
        (field (name "MANUFACTURER PART NUMBER") "CRCW201028R7FKEF")
      )
      (libsource (lib "BMS_Lib") (part "R_28.7OHM_%1_3/4W_2010"))
    )
    (comp (ref "R6")
      (value "28.7R")
      (footprint "R_2010")
      (description "SMD Chip Resistor, 28.7 Ohm, ± 1%, 750 mW, 2010 [5025 Metric], Thick Film, General Purpose")
      (fields
        (field (name "MANUFACTURER") "Vishay Dale")
        (field (name "MANUFACTURER PART NUMBER") "CRCW201028R7FKEF")
      )
      (libsource (lib "BMS_Lib") (part "R_28.7OHM_%1_3/4W_2010"))
    )
    (comp (ref "R7")
      (value "28.7R")
      (footprint "R_2010")
      (description "SMD Chip Resistor, 28.7 Ohm, ± 1%, 750 mW, 2010 [5025 Metric], Thick Film, General Purpose")
      (fields
        (field (name "MANUFACTURER") "Vishay Dale")
        (field (name "MANUFACTURER PART NUMBER") "CRCW201028R7FKEF")
      )
      (libsource (lib "BMS_Lib") (part "R_28.7OHM_%1_3/4W_2010"))
    )
    (comp (ref "R8")
      (value "28.7R")
      (footprint "R_2010")
      (description "SMD Chip Resistor, 28.7 Ohm, ± 1%, 750 mW, 2010 [5025 Metric], Thick Film, General Purpose")
      (fields
        (field (name "MANUFACTURER") "Vishay Dale")
        (field (name "MANUFACTURER PART NUMBER") "CRCW201028R7FKEF")
      )
      (libsource (lib "BMS_Lib") (part "R_28.7OHM_%1_3/4W_2010"))
    )
    (comp (ref "R9")
      (value "28.7R")
      (footprint "R_2010")
      (description "SMD Chip Resistor, 28.7 Ohm, ± 1%, 750 mW, 2010 [5025 Metric], Thick Film, General Purpose")
      (fields
        (field (name "MANUFACTURER") "Vishay Dale")
        (field (name "MANUFACTURER PART NUMBER") "CRCW201028R7FKEF")
      )
      (libsource (lib "BMS_Lib") (part "R_28.7OHM_%1_3/4W_2010"))
    )
    (comp (ref "R10")
      (value "28.7R")
      (footprint "R_2010")
      (description "SMD Chip Resistor, 28.7 Ohm, ± 1%, 750 mW, 2010 [5025 Metric], Thick Film, General Purpose")
      (fields
        (field (name "MANUFACTURER") "Vishay Dale")
        (field (name "MANUFACTURER PART NUMBER") "CRCW201028R7FKEF")
      )
      (libsource (lib "BMS_Lib") (part "R_28.7OHM_%1_3/4W_2010"))
    )
    (comp (ref "R11")
      (value "28.7R")
      (footprint "R_2010")
      (description "SMD Chip Resistor, 28.7 Ohm, ± 1%, 750 mW, 2010 [5025 Metric], Thick Film, General Purpose")
      (fields
        (field (name "MANUFACTURER") "Vishay Dale")
        (field (name "MANUFACTURER PART NUMBER") "CRCW201028R7FKEF")
      )
      (libsource (lib "BMS_Lib") (part "R_28.7OHM_%1_3/4W_2010"))
    )
    (comp (ref "R12")
      (value "28.7R")
      (footprint "R_2010")
      (description "SMD Chip Resistor, 28.7 Ohm, ± 1%, 750 mW, 2010 [5025 Metric], Thick Film, General Purpose")
      (fields
        (field (name "MANUFACTURER") "Vishay Dale")
        (field (name "MANUFACTURER PART NUMBER") "CRCW201028R7FKEF")
      )
      (libsource (lib "BMS_Lib") (part "R_28.7OHM_%1_3/4W_2010"))
    )
    (comp (ref "R13")
      (value "28.7R")
      (footprint "R_2010")
      (description "SMD Chip Resistor, 28.7 Ohm, ± 1%, 750 mW, 2010 [5025 Metric], Thick Film, General Purpose")
      (fields
        (field (name "MANUFACTURER") "Vishay Dale")
        (field (name "MANUFACTURER PART NUMBER") "CRCW201028R7FKEF")
      )
      (libsource (lib "BMS_Lib") (part "R_28.7OHM_%1_3/4W_2010"))
    )
    (comp (ref "R14")
      (value "28.7R")
      (footprint "R_2010")
      (description "SMD Chip Resistor, 28.7 Ohm, ± 1%, 750 mW, 2010 [5025 Metric], Thick Film, General Purpose")
      (fields
        (field (name "MANUFACTURER") "Vishay Dale")
        (field (name "MANUFACTURER PART NUMBER") "CRCW201028R7FKEF")
      )
      (libsource (lib "BMS_Lib") (part "R_28.7OHM_%1_3/4W_2010"))
    )
    (comp (ref "R15")
      (value "28.7R")
      (footprint "R_2010")
      (description "SMD Chip Resistor, 28.7 Ohm, ± 1%, 750 mW, 2010 [5025 Metric], Thick Film, General Purpose")
      (fields
        (field (name "MANUFACTURER") "Vishay Dale")
        (field (name "MANUFACTURER PART NUMBER") "CRCW201028R7FKEF")
      )
      (libsource (lib "BMS_Lib") (part "R_28.7OHM_%1_3/4W_2010"))
    )
    (comp (ref "R16")
      (value "1K")
      (footprint "R_0603")
      (description "SMD Chip Resistor, 1 kOhm, ± 5%, 100 mW, 0603 [1608 Metric], Thick Film, General Purpose")
      (fields
        (field (name "MANUFACTURER") "Vishay Dale")
        (field (name "MANUFACTURER PART NUMBER") "CRCW06031K00JNEA")
      )
      (libsource (lib "BMS_Lib") (part "R_1K_%5_1/10W_0603"))
    )
    (comp (ref "R17")
      (value "1K")
      (footprint "R_0603")
      (description "SMD Chip Resistor, 1 kOhm, ± 5%, 100 mW, 0603 [1608 Metric], Thick Film, General Purpose")
      (fields
        (field (name "MANUFACTURER") "Vishay Dale")
        (field (name "MANUFACTURER PART NUMBER") "CRCW06031K00JNEA")
      )
      (libsource (lib "BMS_Lib") (part "R_1K_%5_1/10W_0603"))
    )
    (comp (ref "R18")
      (value "10K")
      (footprint "R_0603")
      (description "SMD Chip Resistor, 10 kOhm, ± 5%, 100 mW, 0603 [1608 Metric], Thick Film, General Purpose")
      (fields
        (field (name "MANUFACTURER") "Vishay Dale")
        (field (name "MANUFACTURER PART NUMBER") "CRCW060310K0JNEA")
      )
      (libsource (lib "BMS_Lib") (part "R_10K_%5_1/10W_0603"))
    )
    (comp (ref "R19")
      (value "1K")
      (footprint "R_0603")
      (description "SMD Chip Resistor, 1 kOhm, ± 5%, 100 mW, 0603 [1608 Metric], Thick Film, General Purpose")
      (fields
        (field (name "MANUFACTURER") "Vishay Dale")
        (field (name "MANUFACTURER PART NUMBER") "CRCW06031K00JNEA")
      )
      (libsource (lib "BMS_Lib") (part "R_1K_%5_1/10W_0603"))
    )
    (comp (ref "R20")
      (value "10K")
      (footprint "R_0603")
      (description "SMD Chip Resistor, 10 kOhm, ± 5%, 100 mW, 0603 [1608 Metric], Thick Film, General Purpose")
      (fields
        (field (name "MANUFACTURER") "Vishay Dale")
        (field (name "MANUFACTURER PART NUMBER") "CRCW060310K0JNEA")
      )
      (libsource (lib "BMS_Lib") (part "R_10K_%5_1/10W_0603"))
    )
    (comp (ref "R21")
      (value "1K")
      (footprint "R_0603")
      (description "SMD Chip Resistor, 1 kOhm, ± 5%, 100 mW, 0603 [1608 Metric], Thick Film, General Purpose")
      (fields
        (field (name "MANUFACTURER") "Vishay Dale")
        (field (name "MANUFACTURER PART NUMBER") "CRCW06031K00JNEA")
      )
      (libsource (lib "BMS_Lib") (part "R_1K_%5_1/10W_0603"))
    )
    (comp (ref "R22")
      (value "10K")
      (footprint "R_0603")
      (description "SMD Chip Resistor, 10 kOhm, ± 5%, 100 mW, 0603 [1608 Metric], Thick Film, General Purpose")
      (fields
        (field (name "MANUFACTURER") "Vishay Dale")
        (field (name "MANUFACTURER PART NUMBER") "CRCW060310K0JNEA")
      )
      (libsource (lib "BMS_Lib") (part "R_10K_%5_1/10W_0603"))
    )
    (comp (ref "R23")
      (value "1K")
      (footprint "R_0603")
      (description "SMD Chip Resistor, 1 kOhm, ± 5%, 100 mW, 0603 [1608 Metric], Thick Film, General Purpose")
      (fields
        (field (name "MANUFACTURER") "Vishay Dale")
        (field (name "MANUFACTURER PART NUMBER") "CRCW06031K00JNEA")
      )
      (libsource (lib "BMS_Lib") (part "R_1K_%5_1/10W_0603"))
    )
    (comp (ref "R24")
      (value "10K")
      (footprint "R_0603")
      (description "SMD Chip Resistor, 10 kOhm, ± 5%, 100 mW, 0603 [1608 Metric], Thick Film, General Purpose")
      (fields
        (field (name "MANUFACTURER") "Vishay Dale")
        (field (name "MANUFACTURER PART NUMBER") "CRCW060310K0JNEA")
      )
      (libsource (lib "BMS_Lib") (part "R_10K_%5_1/10W_0603"))
    )
    (comp (ref "R25")
      (value "1K")
      (footprint "R_0603")
      (description "SMD Chip Resistor, 1 kOhm, ± 5%, 100 mW, 0603 [1608 Metric], Thick Film, General Purpose")
      (fields
        (field (name "MANUFACTURER") "Vishay Dale")
        (field (name "MANUFACTURER PART NUMBER") "CRCW06031K00JNEA")
      )
      (libsource (lib "BMS_Lib") (part "R_1K_%5_1/10W_0603"))
    )
    (comp (ref "R26")
      (value "10K")
      (footprint "R_0603")
      (description "SMD Chip Resistor, 10 kOhm, ± 5%, 100 mW, 0603 [1608 Metric], Thick Film, General Purpose")
      (fields
        (field (name "MANUFACTURER") "Vishay Dale")
        (field (name "MANUFACTURER PART NUMBER") "CRCW060310K0JNEA")
      )
      (libsource (lib "BMS_Lib") (part "R_10K_%5_1/10W_0603"))
    )
    (comp (ref "R27")
      (value "1K")
      (footprint "R_0603")
      (description "SMD Chip Resistor, 1 kOhm, ± 5%, 100 mW, 0603 [1608 Metric], Thick Film, General Purpose")
      (fields
        (field (name "MANUFACTURER") "Vishay Dale")
        (field (name "MANUFACTURER PART NUMBER") "CRCW06031K00JNEA")
      )
      (libsource (lib "BMS_Lib") (part "R_1K_%5_1/10W_0603"))
    )
    (comp (ref "R28")
      (value "1K")
      (footprint "R_0603")
      (description "SMD Chip Resistor, 1 kOhm, ± 5%, 100 mW, 0603 [1608 Metric], Thick Film, General Purpose")
      (fields
        (field (name "MANUFACTURER") "Vishay Dale")
        (field (name "MANUFACTURER PART NUMBER") "CRCW06031K00JNEA")
      )
      (libsource (lib "BMS_Lib") (part "R_1K_%5_1/10W_0603"))
    )
    (comp (ref "R29")
      (value "1K")
      (footprint "R_0603")
      (description "SMD Chip Resistor, 1 kOhm, ± 5%, 100 mW, 0603 [1608 Metric], Thick Film, General Purpose")
      (fields
        (field (name "MANUFACTURER") "Vishay Dale")
        (field (name "MANUFACTURER PART NUMBER") "CRCW06031K00JNEA")
      )
      (libsource (lib "BMS_Lib") (part "R_1K_%5_1/10W_0603"))
    )
    (comp (ref "R30")
      (value "10K")
      (footprint "R_0603")
      (description "SMD Chip Resistor, 10 kOhm, ± 5%, 100 mW, 0603 [1608 Metric], Thick Film, General Purpose")
      (fields
        (field (name "MANUFACTURER") "Vishay Dale")
        (field (name "MANUFACTURER PART NUMBER") "CRCW060310K0JNEA")
      )
      (libsource (lib "BMS_Lib") (part "R_10K_%5_1/10W_0603"))
    )
    (comp (ref "R31")
      (value "1K")
      (footprint "R_0603")
      (description "SMD Chip Resistor, 1 kOhm, ± 5%, 100 mW, 0603 [1608 Metric], Thick Film, General Purpose")
      (fields
        (field (name "MANUFACTURER") "Vishay Dale")
        (field (name "MANUFACTURER PART NUMBER") "CRCW06031K00JNEA")
      )
      (libsource (lib "BMS_Lib") (part "R_1K_%5_1/10W_0603"))
    )
    (comp (ref "R32")
      (value "10K")
      (footprint "R_0603")
      (description "SMD Chip Resistor, 10 kOhm, ± 5%, 100 mW, 0603 [1608 Metric], Thick Film, General Purpose")
      (fields
        (field (name "MANUFACTURER") "Vishay Dale")
        (field (name "MANUFACTURER PART NUMBER") "CRCW060310K0JNEA")
      )
      (libsource (lib "BMS_Lib") (part "R_10K_%5_1/10W_0603"))
    )
    (comp (ref "R33")
      (value "1K")
      (footprint "R_0603")
      (description "SMD Chip Resistor, 1 kOhm, ± 5%, 100 mW, 0603 [1608 Metric], Thick Film, General Purpose")
      (fields
        (field (name "MANUFACTURER") "Vishay Dale")
        (field (name "MANUFACTURER PART NUMBER") "CRCW06031K00JNEA")
      )
      (libsource (lib "BMS_Lib") (part "R_1K_%5_1/10W_0603"))
    )
    (comp (ref "R34")
      (value "10K")
      (footprint "R_0603")
      (description "SMD Chip Resistor, 10 kOhm, ± 5%, 100 mW, 0603 [1608 Metric], Thick Film, General Purpose")
      (fields
        (field (name "MANUFACTURER") "Vishay Dale")
        (field (name "MANUFACTURER PART NUMBER") "CRCW060310K0JNEA")
      )
      (libsource (lib "BMS_Lib") (part "R_10K_%5_1/10W_0603"))
    )
    (comp (ref "R35")
      (value "1K")
      (footprint "R_0603")
      (description "SMD Chip Resistor, 1 kOhm, ± 5%, 100 mW, 0603 [1608 Metric], Thick Film, General Purpose")
      (fields
        (field (name "MANUFACTURER") "Vishay Dale")
        (field (name "MANUFACTURER PART NUMBER") "CRCW06031K00JNEA")
      )
      (libsource (lib "BMS_Lib") (part "R_1K_%5_1/10W_0603"))
    )
    (comp (ref "R36")
      (value "10K")
      (footprint "R_0603")
      (description "SMD Chip Resistor, 10 kOhm, ± 5%, 100 mW, 0603 [1608 Metric], Thick Film, General Purpose")
      (fields
        (field (name "MANUFACTURER") "Vishay Dale")
        (field (name "MANUFACTURER PART NUMBER") "CRCW060310K0JNEA")
      )
      (libsource (lib "BMS_Lib") (part "R_10K_%5_1/10W_0603"))
    )
    (comp (ref "R37")
      (value "1K")
      (footprint "R_0603")
      (description "SMD Chip Resistor, 1 kOhm, ± 5%, 100 mW, 0603 [1608 Metric], Thick Film, General Purpose")
      (fields
        (field (name "MANUFACTURER") "Vishay Dale")
        (field (name "MANUFACTURER PART NUMBER") "CRCW06031K00JNEA")
      )
      (libsource (lib "BMS_Lib") (part "R_1K_%5_1/10W_0603"))
    )
    (comp (ref "R38")
      (value "10K")
      (footprint "R_0603")
      (description "SMD Chip Resistor, 10 kOhm, ± 5%, 100 mW, 0603 [1608 Metric], Thick Film, General Purpose")
      (fields
        (field (name "MANUFACTURER") "Vishay Dale")
        (field (name "MANUFACTURER PART NUMBER") "CRCW060310K0JNEA")
      )
      (libsource (lib "BMS_Lib") (part "R_10K_%5_1/10W_0603"))
    )
    (comp (ref "R39")
      (value "1K")
      (footprint "R_0603")
      (description "SMD Chip Resistor, 1 kOhm, ± 5%, 100 mW, 0603 [1608 Metric], Thick Film, General Purpose")
      (fields
        (field (name "MANUFACTURER") "Vishay Dale")
        (field (name "MANUFACTURER PART NUMBER") "CRCW06031K00JNEA")
      )
      (libsource (lib "BMS_Lib") (part "R_1K_%5_1/10W_0603"))
    )
    (comp (ref "R40")
      (value "1K")
      (footprint "R_0603")
      (description "SMD Chip Resistor, 1 kOhm, ± 5%, 100 mW, 0603 [1608 Metric], Thick Film, General Purpose")
      (fields
        (field (name "MANUFACTURER") "Vishay Dale")
        (field (name "MANUFACTURER PART NUMBER") "CRCW06031K00JNEA")
      )
      (libsource (lib "BMS_Lib") (part "R_1K_%5_1/10W_0603"))
    )
    (comp (ref "R41")
      (value "1K")
      (footprint "R_0603")
      (description "SMD Chip Resistor, 1 kOhm, ± 5%, 100 mW, 0603 [1608 Metric], Thick Film, General Purpose")
      (fields
        (field (name "MANUFACTURER") "Vishay Dale")
        (field (name "MANUFACTURER PART NUMBER") "CRCW06031K00JNEA")
      )
      (libsource (lib "BMS_Lib") (part "R_1K_%5_1/10W_0603"))
    )
    (comp (ref "R42")
      (value "10K")
      (footprint "R_0603")
      (description "SMD Chip Resistor, 10 kOhm, ± 5%, 100 mW, 0603 [1608 Metric], Thick Film, General Purpose")
      (fields
        (field (name "MANUFACTURER") "Vishay Dale")
        (field (name "MANUFACTURER PART NUMBER") "CRCW060310K0JNEA")
      )
      (libsource (lib "BMS_Lib") (part "R_10K_%5_1/10W_0603"))
    )
    (comp (ref "R43")
      (value "1K")
      (footprint "R_0603")
      (description "SMD Chip Resistor, 1 kOhm, ± 5%, 100 mW, 0603 [1608 Metric], Thick Film, General Purpose")
      (fields
        (field (name "MANUFACTURER") "Vishay Dale")
        (field (name "MANUFACTURER PART NUMBER") "CRCW06031K00JNEA")
      )
      (libsource (lib "BMS_Lib") (part "R_1K_%5_1/10W_0603"))
    )
    (comp (ref "R44")
      (value "10K")
      (footprint "R_0603")
      (description "SMD Chip Resistor, 10 kOhm, ± 5%, 100 mW, 0603 [1608 Metric], Thick Film, General Purpose")
      (fields
        (field (name "MANUFACTURER") "Vishay Dale")
        (field (name "MANUFACTURER PART NUMBER") "CRCW060310K0JNEA")
      )
      (libsource (lib "BMS_Lib") (part "R_10K_%5_1/10W_0603"))
    )
    (comp (ref "R45")
      (value "1K")
      (footprint "R_0603")
      (description "SMD Chip Resistor, 1 kOhm, ± 5%, 100 mW, 0603 [1608 Metric], Thick Film, General Purpose")
      (fields
        (field (name "MANUFACTURER") "Vishay Dale")
        (field (name "MANUFACTURER PART NUMBER") "CRCW06031K00JNEA")
      )
      (libsource (lib "BMS_Lib") (part "R_1K_%5_1/10W_0603"))
    )
    (comp (ref "R46")
      (value "10K")
      (footprint "R_0603")
      (description "SMD Chip Resistor, 10 kOhm, ± 5%, 100 mW, 0603 [1608 Metric], Thick Film, General Purpose")
      (fields
        (field (name "MANUFACTURER") "Vishay Dale")
        (field (name "MANUFACTURER PART NUMBER") "CRCW060310K0JNEA")
      )
      (libsource (lib "BMS_Lib") (part "R_10K_%5_1/10W_0603"))
    )
    (comp (ref "R47")
      (value "1K")
      (footprint "R_0603")
      (description "SMD Chip Resistor, 1 kOhm, ± 5%, 100 mW, 0603 [1608 Metric], Thick Film, General Purpose")
      (fields
        (field (name "MANUFACTURER") "Vishay Dale")
        (field (name "MANUFACTURER PART NUMBER") "CRCW06031K00JNEA")
      )
      (libsource (lib "BMS_Lib") (part "R_1K_%5_1/10W_0603"))
    )
    (comp (ref "R48")
      (value "10K")
      (footprint "R_0603")
      (description "SMD Chip Resistor, 10 kOhm, ± 5%, 100 mW, 0603 [1608 Metric], Thick Film, General Purpose")
      (fields
        (field (name "MANUFACTURER") "Vishay Dale")
        (field (name "MANUFACTURER PART NUMBER") "CRCW060310K0JNEA")
      )
      (libsource (lib "BMS_Lib") (part "R_10K_%5_1/10W_0603"))
    )
    (comp (ref "R49")
      (value "1K")
      (footprint "R_0603")
      (description "SMD Chip Resistor, 1 kOhm, ± 5%, 100 mW, 0603 [1608 Metric], Thick Film, General Purpose")
      (fields
        (field (name "MANUFACTURER") "Vishay Dale")
        (field (name "MANUFACTURER PART NUMBER") "CRCW06031K00JNEA")
      )
      (libsource (lib "BMS_Lib") (part "R_1K_%5_1/10W_0603"))
    )
    (comp (ref "R50")
      (value "10K")
      (footprint "R_0603")
      (description "SMD Chip Resistor, 10 kOhm, ± 5%, 100 mW, 0603 [1608 Metric], Thick Film, General Purpose")
      (fields
        (field (name "MANUFACTURER") "Vishay Dale")
        (field (name "MANUFACTURER PART NUMBER") "CRCW060310K0JNEA")
      )
      (libsource (lib "BMS_Lib") (part "R_10K_%5_1/10W_0603"))
    )
    (comp (ref "R51")
      (value "1K")
      (footprint "R_0603")
      (description "SMD Chip Resistor, 1 kOhm, ± 5%, 100 mW, 0603 [1608 Metric], Thick Film, General Purpose")
      (fields
        (field (name "MANUFACTURER") "Vishay Dale")
        (field (name "MANUFACTURER PART NUMBER") "CRCW06031K00JNEA")
      )
      (libsource (lib "BMS_Lib") (part "R_1K_%5_1/10W_0603"))
    )
    (comp (ref "R52")
      (value "0R")
      (footprint "R_0603")
      (description "Zero Ohm Resistor, Jumper, 0603 [1608 Metric], Thick Film, 330 mW, 5 A, Surface Mount")
      (fields
        (field (name "MANUFACTURER") "Vishay Dale")
        (field (name "MANUFACTURER PART NUMBER") "CRCW06030000Z0EAHP")
      )
      (libsource (lib "BMS_Lib") (part "R_0OHM_1/10W_0603"))
    )
    (comp (ref "R53")
      (value "0R")
      (footprint "R_0603")
      (description "Zero Ohm Resistor, Jumper, 0603 [1608 Metric], Thick Film, 330 mW, 5 A, Surface Mount")
      (fields
        (field (name "MANUFACTURER") "Vishay Dale")
        (field (name "MANUFACTURER PART NUMBER") "CRCW06030000Z0EAHP")
      )
      (libsource (lib "BMS_Lib") (part "R_0OHM_1/10W_0603"))
    )
    (comp (ref "R54")
      (value "0R")
      (footprint "R_0603")
      (description "Zero Ohm Resistor, Jumper, 0603 [1608 Metric], Thick Film, 330 mW, 5 A, Surface Mount")
      (fields
        (field (name "MANUFACTURER") "Vishay Dale")
        (field (name "MANUFACTURER PART NUMBER") "CRCW06030000Z0EAHP")
      )
      (libsource (lib "BMS_Lib") (part "R_0OHM_1/10W_0603"))
    )
    (comp (ref "R55")
      (value "499K")
      (footprint "R_0603")
      (description "SMD Chip Resistor, 499 kOhm, ± 1%, 100 mW, 0603 [1608 Metric], Thick Film, General Purpose")
      (fields
        (field (name "MANUFACTURER") "Vishay")
        (field (name "MANUFACTURER PART NUMBER") "CRCW0603499KFKEA")
      )
      (libsource (lib "BMS_Lib") (part "R_499K_%1_1/10W_0603"))
    )
    (comp (ref "R56")
      (value "100R")
      (footprint "R_0805")
      (description "SMD Chip Resistor, 100 Ohm, ± 1%, 125 mW, 0805 [2012 Metric], Thick Film, General Purpose")
      (fields
        (field (name "MANUFACTURER") "Vishay Dale")
        (field (name "MANUFACTURER PART NUMBER") "CRCW0805100RFKEA")
      )
      (libsource (lib "BMS_Lib") (part "R_100OHM_%1_1/8W_0805"))
    )
    (comp (ref "R57")
      (value "100R")
      (footprint "R_0805")
      (description "SMD Chip Resistor, 100 Ohm, ± 1%, 125 mW, 0805 [2012 Metric], Thick Film, General Purpose")
      (fields
        (field (name "MANUFACTURER") "Vishay Dale")
        (field (name "MANUFACTURER PART NUMBER") "CRCW0805100RFKEA")
      )
      (libsource (lib "BMS_Lib") (part "R_100OHM_%1_1/8W_0805"))
    )
    (comp (ref "R58")
      (value "10K")
      (footprint "R_0603")
      (description "SMD Chip Resistor, 10 kOhm, ± 5%, 100 mW, 0603 [1608 Metric], Thick Film, General Purpose")
      (fields
        (field (name "MANUFACTURER") "Vishay Dale")
        (field (name "MANUFACTURER PART NUMBER") "CRCW060310K0JNEA")
      )
      (libsource (lib "BMS_Lib") (part "R_10K_%5_1/10W_0603"))
    )
    (comp (ref "R59")
      (value "100K")
      (footprint "R_0805")
      (description "SMD Chip Resistor, 100 kOhm, ± 1%, 125 mW, 0805 [2012 Metric], Thick Film, General Purpose")
      (fields
        (field (name "MANUFACTURER") "Vishay")
        (field (name "MANUFACTURER PART NUMBER") "CRCW0805100KFKEA")
      )
      (libsource (lib "BMS_Lib") (part "R_100K_%1_1/8W_0805"))
    )
    (comp (ref "R60")
      (value "10K")
      (footprint "R_0603")
      (description "SMD Chip Resistor, 10 kOhm, ± 5%, 100 mW, 0603 [1608 Metric], Thick Film, General Purpose")
      (fields
        (field (name "MANUFACTURER") "Vishay Dale")
        (field (name "MANUFACTURER PART NUMBER") "CRCW060310K0JNEA")
      )
      (libsource (lib "BMS_Lib") (part "R_10K_%5_1/10W_0603"))
    )
    (comp (ref "R61")
      (value "100K")
      (footprint "R_0805")
      (description "SMD Chip Resistor, 100 kOhm, ± 1%, 125 mW, 0805 [2012 Metric], Thick Film, General Purpose")
      (fields
        (field (name "MANUFACTURER") "Vishay")
        (field (name "MANUFACTURER PART NUMBER") "CRCW0805100KFKEA")
      )
      (libsource (lib "BMS_Lib") (part "R_100K_%1_1/8W_0805"))
    )
    (comp (ref "R62")
      (value "1K")
      (footprint "R_2010")
      (description "Res Thick Film 2010 1K Ohm 5% 0.75W(3/4W) ±200ppm/°C Pad SMD Automotive T/R")
      (fields
        (field (name "MANUFACTURER") "Vishay Dale")
        (field (name "MANUFACTURER PART NUMBER") "CRCW20101K00JNEF")
      )
      (libsource (lib "BMS_Lib") (part "R_1K_%5_3/4W_2010"))
    )
    (comp (ref "R63")
      (value "750R")
      (footprint "R_2010")
      (description "SMD Chip Resistor, 750 Ohm, ± 5%, 750 mW, 2010 [5025 Metric], Thick Film, General Purpose")
      (fields
        (field (name "MANUFACTURER") "Vishay Dale")
        (field (name "MANUFACTURER PART NUMBER") "CRCW2010750RJNEF")
      )
      (libsource (lib "BMS_Lib") (part "R_750OHM_%5_3/4W_2010"))
    )
    (comp (ref "R64")
      (value "51K")
      (footprint "R_0603")
      (description "SMD Chip Resistor, 51 kOhm, ± 5%, 100 mW, 0603 [1608 Metric], Thick Film, General Purpose")
      (fields
        (field (name "MANUFACTURER") "Vishay Dale")
        (field (name "MANUFACTURER PART NUMBER") "CRCW060351K0JNEA")
      )
      (libsource (lib "BMS_Lib") (part "R_51K_%5_1/10W_0603"))
    )
    (comp (ref "R65")
      (value "10M")
      (footprint "R_0603")
      (description "SMD Chip Resistor, 10 MOhm, ± 1%, 100 mW, 0603 [1608 Metric], Thick Film, General Purpose")
      (fields
        (field (name "MANUFACTURER") "Vishay")
        (field (name "MANUFACTURER PART NUMBER") "CRCW060310M0FKEA")
      )
      (libsource (lib "BMS_Lib") (part "R_10M_%1_1/10W_0603"))
    )
    (comp (ref "R66")
      (value "1K")
      (footprint "R_0603")
      (description "SMD Chip Resistor, 1 kOhm, ± 5%, 100 mW, 0603 [1608 Metric], Thick Film, General Purpose")
      (fields
        (field (name "MANUFACTURER") "Vishay Dale")
        (field (name "MANUFACTURER PART NUMBER") "CRCW06031K00JNEA")
      )
      (libsource (lib "BMS_Lib") (part "R_1K_%5_1/10W_0603"))
    )
    (comp (ref "R67")
      (value "100K")
      (footprint "R_0805")
      (description "SMD Chip Resistor, 100 kOhm, ± 1%, 125 mW, 0805 [2012 Metric], Thick Film, General Purpose")
      (fields
        (field (name "MANUFACTURER") "Vishay")
        (field (name "MANUFACTURER PART NUMBER") "CRCW0805100KFKEA")
      )
      (libsource (lib "BMS_Lib") (part "R_100K_%1_1/8W_0805"))
    )
    (comp (ref "R68")
      (value "1K")
      (footprint "R_0603")
      (description "SMD Chip Resistor, 1 kOhm, ± 5%, 100 mW, 0603 [1608 Metric], Thick Film, General Purpose")
      (fields
        (field (name "MANUFACTURER") "Vishay Dale")
        (field (name "MANUFACTURER PART NUMBER") "CRCW06031K00JNEA")
      )
      (libsource (lib "BMS_Lib") (part "R_1K_%5_1/10W_0603"))
    )
    (comp (ref "R69")
      (value "10M")
      (footprint "R_0603")
      (description "SMD Chip Resistor, 10 MOhm, ± 1%, 100 mW, 0603 [1608 Metric], Thick Film, General Purpose")
      (fields
        (field (name "MANUFACTURER") "Vishay")
        (field (name "MANUFACTURER PART NUMBER") "CRCW060310M0FKEA")
      )
      (libsource (lib "BMS_Lib") (part "R_10M_%1_1/10W_0603"))
    )
    (comp (ref "R70")
      (value "1M")
      (footprint "R_0603")
      (description "SMD Chip Resistor, 1 MOhm, ± 5%, 100 mW, 0603 [1608 Metric], Thick Film, General Purpose")
      (fields
        (field (name "MANUFACTURER") "Vishay Dale")
        (field (name "MANUFACTURER PART NUMBER") "CRCW06031M00JNEA")
      )
      (libsource (lib "BMS_Lib") (part "R_1M_%5_1/10W_0603"))
    )
    (comp (ref "RT1")
      (value "10K")
      (footprint "NTC")
      (description "Thermistor NTC 10KOhm 1% 2-Pin")
      (fields (field (name "MANUFACTURER") "Semitec") (field (name "MANUFACTURER PART NUMBER") "103AT-2"))
      (libsource (lib "BMS_Lib") (part "NTC_TERMISTOR_10K_%1"))
    )
    (comp (ref "RT2")
      (value "10K")
      (footprint "NTC")
      (description "Thermistor NTC 10KOhm 1% 2-Pin")
      (fields (field (name "MANUFACTURER") "Semitec") (field (name "MANUFACTURER PART NUMBER") "103AT-2"))
      (libsource (lib "BMS_Lib") (part "NTC_TERMISTOR_10K_%1"))
    )
    (comp (ref "RT3")
      (value "10K")
      (footprint "NTC")
      (description "Thermistor NTC 10KOhm 1% 2-Pin")
      (fields (field (name "MANUFACTURER") "Semitec") (field (name "MANUFACTURER PART NUMBER") "103AT-2"))
      (libsource (lib "BMS_Lib") (part "NTC_TERMISTOR_10K_%1"))
    )
    (comp (ref "TP1")
      (value "PEC02SAAN")
      (footprint "TP_2POS")
      (description "Conn Unshrouded Header HDR 2 POS 2.54mm Solder ST Top Entry Thru-Hole")
      (fields (field (name "MANUFACTURER") "Sullins"))
      (libsource (lib "BMS_Lib") (part "TP_CONN_2POS_2.54MM"))
    )
    (comp (ref "TP2")
      (value "5011")
      (footprint "TP_VİA")
      (fields (field (name "MANUFACTURER") "Keystone Electronics"))
      (libsource (lib "BMS_Lib") (part "TP_PC_TEST_POİNT"))
    )
    (comp (ref "TP3")
      (value "5011")
      (footprint "TP_VİA")
      (fields (field (name "MANUFACTURER") "Keystone Electronics"))
      (libsource (lib "BMS_Lib") (part "TP_PC_TEST_POİNT"))
    )
    (comp (ref "TP4") (value "TEST POİNT") (footprint "TP_GND") (libsource (lib "BMS_Lib") (part "TP_GND")))
    (comp (ref "TP5") (value "TEST POİNT") (footprint "TP_GND") (libsource (lib "BMS_Lib") (part "TP_GND")))
    (comp (ref "TP6") (value "TEST POİNT") (footprint "TP_GND") (libsource (lib "BMS_Lib") (part "TP_GND")))
    (comp (ref "TP7") (value "TEST POİNT") (footprint "TP_GND") (libsource (lib "BMS_Lib") (part "TP_GND")))
    (comp (ref "TP8")
      (value "5011")
      (footprint "TP_VİA")
      (fields (field (name "MANUFACTURER") "Keystone Electronics"))
      (libsource (lib "BMS_Lib") (part "TP_PC_TEST_POİNT"))
    )
    (comp (ref "TP9")
      (value "5011")
      (footprint "TP_VİA")
      (fields (field (name "MANUFACTURER") "Keystone Electronics"))
      (libsource (lib "BMS_Lib") (part "TP_PC_TEST_POİNT"))
    )
    (comp (ref "TP10")
      (value "5011")
      (footprint "TP_VİA")
      (fields (field (name "MANUFACTURER") "Keystone Electronics"))
      (libsource (lib "BMS_Lib") (part "TP_PC_TEST_POİNT"))
    )
    (comp (ref "TP11")
      (value "5011")
      (footprint "TP_VİA")
      (fields (field (name "MANUFACTURER") "Keystone Electronics"))
      (libsource (lib "BMS_Lib") (part "TP_PC_TEST_POİNT"))
    )
    (comp (ref "TP12")
      (value "5011")
      (footprint "TP_VİA")
      (fields (field (name "MANUFACTURER") "Keystone Electronics"))
      (libsource (lib "BMS_Lib") (part "TP_PC_TEST_POİNT"))
    )
    (comp (ref "TP13")
      (value "5011")
      (footprint "TP_VİA")
      (fields (field (name "MANUFACTURER") "Keystone Electronics"))
      (libsource (lib "BMS_Lib") (part "TP_PC_TEST_POİNT"))
    )
    (comp (ref "TP14")
      (value "5011")
      (footprint "TP_VİA")
      (fields (field (name "MANUFACTURER") "Keystone Electronics"))
      (libsource (lib "BMS_Lib") (part "TP_PC_TEST_POİNT"))
    )
    (comp (ref "TP15")
      (value "5011")
      (footprint "TP_VİA")
      (fields (field (name "MANUFACTURER") "Keystone Electronics"))
      (libsource (lib "BMS_Lib") (part "TP_PC_TEST_POİNT"))
    )
    (comp (ref "U1")
      (value "BQ7694000DBTR")
      (footprint "44TSSOP")
      (description "9 to 15-series cell li-ion and li-phosphate battery monitor (bq76940 family) 44-TSSOP -40 to 85")
      (fields (field (name "MANUFACTURER") "Texas Instruments"))
      (libsource (lib "BMS_Lib") (part "AFE_IC_44TSSOP"))
    )
  )
  (nets
    (net (code "1") (name "/ALERT") (class "Default")
      (node (ref "C21") (pin "2") (pinfunction "2_2") (pintype "passive"))
      (node (ref "R55") (pin "2") (pinfunction "2_2") (pintype "passive"))
      (node (ref "TP9") (pin "1") (pinfunction "1_1") (pintype "passive"))
      (node (ref "U1") (pin "44") (pinfunction "ALERT_44") (pintype "passive"))
    )
    (net (code "2") (name "/C0") (class "Default")
      (node (ref "D14") (pin "2") (pinfunction "2_2") (pintype "passive"))
      (node (ref "J2") (pin "11") (pinfunction "11_11") (pintype "passive"))
      (node (ref "Q15") (pin "2") (pinfunction "S_2") (pintype "passive"))
      (node (ref "R51") (pin "1") (pinfunction "1_1") (pintype "passive"))
    )
    (net (code "3") (name "/C1") (class "Default")
      (node (ref "D13") (pin "2") (pinfunction "2_2") (pintype "passive"))
      (node (ref "J2") (pin "10") (pinfunction "10_10") (pintype "passive"))
      (node (ref "Q14") (pin "2") (pinfunction "S_2") (pintype "passive"))
      (node (ref "R49") (pin "1") (pinfunction "1_1") (pintype "passive"))
      (node (ref "R6") (pin "1") (pinfunction "1_1") (pintype "passive"))
    )
    (net (code "4") (name "/C2") (class "Default")
      (node (ref "D12") (pin "2") (pinfunction "2_2") (pintype "passive"))
      (node (ref "J2") (pin "9") (pinfunction "9_9") (pintype "passive"))
      (node (ref "Q13") (pin "2") (pinfunction "S_2") (pintype "passive"))
      (node (ref "R47") (pin "1") (pinfunction "1_1") (pintype "passive"))
      (node (ref "R5") (pin "1") (pinfunction "1_1") (pintype "passive"))
    )
    (net (code "5") (name "/C3") (class "Default")
      (node (ref "D11") (pin "2") (pinfunction "2_2") (pintype "passive"))
      (node (ref "J2") (pin "8") (pinfunction "8_8") (pintype "passive"))
      (node (ref "Q12") (pin "2") (pinfunction "S_2") (pintype "passive"))
      (node (ref "R4") (pin "1") (pinfunction "1_1") (pintype "passive"))
      (node (ref "R45") (pin "1") (pinfunction "1_1") (pintype "passive"))
    )
    (net (code "6") (name "/C4") (class "Default")
      (node (ref "D10") (pin "2") (pinfunction "2_2") (pintype "passive"))
      (node (ref "J2") (pin "7") (pinfunction "7_7") (pintype "passive"))
      (node (ref "Q11") (pin "2") (pinfunction "S_2") (pintype "passive"))
      (node (ref "R1") (pin "1") (pinfunction "1_1") (pintype "passive"))
      (node (ref "R43") (pin "1") (pinfunction "1_1") (pintype "passive"))
    )
    (net (code "7") (name "/C5") (class "Default")
      (node (ref "D1") (pin "2") (pinfunction "2_2") (pintype "passive"))
      (node (ref "J2") (pin "6") (pinfunction "6_6") (pintype "passive"))
      (node (ref "Q10") (pin "2") (pinfunction "S_2") (pintype "passive"))
      (node (ref "R3") (pin "1") (pinfunction "1_1") (pintype "passive"))
      (node (ref "R39") (pin "1") (pinfunction "1_1") (pintype "passive"))
      (node (ref "R40") (pin "1") (pinfunction "1_1") (pintype "passive"))
      (node (ref "R41") (pin "1") (pinfunction "1_1") (pintype "passive"))
    )
    (net (code "8") (name "/C6") (class "Default")
      (node (ref "D9") (pin "2") (pinfunction "2_2") (pintype "passive"))
      (node (ref "J2") (pin "5") (pinfunction "5_5") (pintype "passive"))
      (node (ref "Q9") (pin "2") (pinfunction "S_2") (pintype "passive"))
      (node (ref "R2") (pin "1") (pinfunction "1_1") (pintype "passive"))
      (node (ref "R37") (pin "1") (pinfunction "1_1") (pintype "passive"))
    )
    (net (code "9") (name "/C7") (class "Default")
      (node (ref "D8") (pin "2") (pinfunction "2_2") (pintype "passive"))
      (node (ref "J2") (pin "4") (pinfunction "4_4") (pintype "passive"))
      (node (ref "Q8") (pin "2") (pinfunction "S_2") (pintype "passive"))
      (node (ref "R15") (pin "1") (pinfunction "1_1") (pintype "passive"))
      (node (ref "R35") (pin "1") (pinfunction "1_1") (pintype "passive"))
    )
    (net (code "10") (name "/C8") (class "Default")
      (node (ref "D7") (pin "2") (pinfunction "2_2") (pintype "passive"))
      (node (ref "J2") (pin "3") (pinfunction "3_3") (pintype "passive"))
      (node (ref "Q7") (pin "2") (pinfunction "S_2") (pintype "passive"))
      (node (ref "R14") (pin "1") (pinfunction "1_1") (pintype "passive"))
      (node (ref "R33") (pin "1") (pinfunction "1_1") (pintype "passive"))
    )
    (net (code "11") (name "/C9") (class "Default")
      (node (ref "D6") (pin "2") (pinfunction "2_2") (pintype "passive"))
      (node (ref "J2") (pin "2") (pinfunction "2_2") (pintype "passive"))
      (node (ref "Q6") (pin "2") (pinfunction "S_2") (pintype "passive"))
      (node (ref "R13") (pin "1") (pinfunction "1_1") (pintype "passive"))
      (node (ref "R31") (pin "1") (pinfunction "1_1") (pintype "passive"))
    )
    (net (code "12") (name "/C10") (class "Default")
      (node (ref "D15") (pin "2") (pinfunction "2_2") (pintype "passive"))
      (node (ref "J2") (pin "1") (pinfunction "1_1") (pintype "passive"))
      (node (ref "Q5") (pin "2") (pinfunction "S_2") (pintype "passive"))
      (node (ref "R12") (pin "1") (pinfunction "1_1") (pintype "passive"))
      (node (ref "R27") (pin "1") (pinfunction "1_1") (pintype "passive"))
      (node (ref "R28") (pin "1") (pinfunction "1_1") (pintype "passive"))
      (node (ref "R29") (pin "1") (pinfunction "1_1") (pintype "passive"))
    )
    (net (code "13") (name "/C11") (class "Default")
      (node (ref "D5") (pin "2") (pinfunction "2_2") (pintype "passive"))
      (node (ref "J1") (pin "5") (pinfunction "5_5") (pintype "passive"))
      (node (ref "Q4") (pin "2") (pinfunction "S_2") (pintype "passive"))
      (node (ref "R11") (pin "1") (pinfunction "1_1") (pintype "passive"))
      (node (ref "R25") (pin "1") (pinfunction "1_1") (pintype "passive"))
    )
    (net (code "14") (name "/C12") (class "Default")
      (node (ref "D4") (pin "2") (pinfunction "2_2") (pintype "passive"))
      (node (ref "J1") (pin "4") (pinfunction "4_4") (pintype "passive"))
      (node (ref "Q3") (pin "2") (pinfunction "S_2") (pintype "passive"))
      (node (ref "R10") (pin "1") (pinfunction "1_1") (pintype "passive"))
      (node (ref "R23") (pin "1") (pinfunction "1_1") (pintype "passive"))
    )
    (net (code "15") (name "/C13") (class "Default")
      (node (ref "D3") (pin "2") (pinfunction "2_2") (pintype "passive"))
      (node (ref "J1") (pin "3") (pinfunction "3_3") (pintype "passive"))
      (node (ref "Q2") (pin "2") (pinfunction "S_2") (pintype "passive"))
      (node (ref "R21") (pin "1") (pinfunction "1_1") (pintype "passive"))
      (node (ref "R9") (pin "1") (pinfunction "1_1") (pintype "passive"))
    )
    (net (code "16") (name "/C14") (class "Default")
      (node (ref "D2") (pin "2") (pinfunction "2_2") (pintype "passive"))
      (node (ref "J1") (pin "2") (pinfunction "2_2") (pintype "passive"))
      (node (ref "Q1") (pin "2") (pinfunction "S_2") (pintype "passive"))
      (node (ref "R19") (pin "1") (pinfunction "1_1") (pintype "passive"))
      (node (ref "R8") (pin "1") (pinfunction "1_1") (pintype "passive"))
    )
    (net (code "17") (name "/C15") (class "Default")
      (node (ref "C36") (pin "1") (pinfunction "1_1") (pintype "passive"))
      (node (ref "D19") (pin "2") (pinfunction "2_2") (pintype "passive"))
      (node (ref "J1") (pin "1") (pinfunction "1_1") (pintype "passive"))
      (node (ref "R16") (pin "1") (pinfunction "1_1") (pintype "passive"))
      (node (ref "R17") (pin "1") (pinfunction "1_1") (pintype "passive"))
      (node (ref "R61") (pin "2") (pinfunction "2_2") (pintype "passive"))
      (node (ref "R63") (pin "2") (pinfunction "2_2") (pintype "passive"))
      (node (ref "R7") (pin "1") (pinfunction "1_1") (pintype "passive"))
    )
    (net (code "18") (name "/CAP1") (class "Default")
      (node (ref "C28") (pin "2") (pinfunction "2_2") (pintype "passive"))
      (node (ref "Q17") (pin "1") (pinfunction "B_1") (pintype "passive"))
      (node (ref "U1") (pin "7") (pinfunction "CAP1_7") (pintype "passive"))
    )
    (net (code "19") (name "/CAP2") (class "Default")
      (node (ref "C27") (pin "1") (pinfunction "1_1") (pintype "passive"))
      (node (ref "U1") (pin "11") (pinfunction "NC_11") (pintype "passive"))
      (node (ref "U1") (pin "12") (pinfunction "NC_12") (pintype "passive"))
      (node (ref "U1") (pin "14") (pinfunction "CAP2_14") (pintype "passive"))
    )
    (net (code "20") (name "/CAP3") (class "Default")
      (node (ref "C26") (pin "1") (pinfunction "1_1") (pintype "passive"))
      (node (ref "U1") (pin "16") (pinfunction "NC_16") (pintype "passive"))
      (node (ref "U1") (pin "17") (pinfunction "NC_17") (pintype "passive"))
      (node (ref "U1") (pin "19") (pinfunction "CAP3_19") (pintype "passive"))
    )
    (net (code "21") (name "/CHG_EN") (class "Default")
      (node (ref "U1") (pin "2") (pinfunction "CHG_2") (pintype "passive"))
    )
    (net (code "22") (name "/DSG_EN") (class "Default")
      (node (ref "U1") (pin "1") (pinfunction "DSG_1") (pintype "passive"))
    )
    (net (code "23") (name "/LEDP") (class "Default")
      (node (ref "C35") (pin "2") (pinfunction "2_2") (pintype "passive"))
      (node (ref "Q17") (pin "3") (pinfunction "E_3") (pintype "passive"))
    )
    (net (code "24") (name "/PACK+") (class "Default")
      (node (ref "D23") (pin "1") (pinfunction "1_1") (pintype "passive"))
      (node (ref "Q19") (pin "2") (pinfunction "S_2") (pintype "passive"))
      (node (ref "R65") (pin "2") (pinfunction "2_2") (pintype "passive"))
    )
    (net (code "25") (name "/REGSRC") (class "Default")
      (node (ref "C33") (pin "2") (pinfunction "2_2") (pintype "passive"))
      (node (ref "Q16") (pin "2") (pinfunction "S_2") (pintype "passive"))
      (node (ref "U1") (pin "9") (pinfunction "REGSRC_9") (pintype "passive"))
    )
    (net (code "26") (name "/SCL") (class "Default")
      (node (ref "R60") (pin "1") (pinfunction "1_1") (pintype "passive"))
      (node (ref "TP3") (pin "1") (pinfunction "1_1") (pintype "passive"))
      (node (ref "U1") (pin "5") (pinfunction "SCL_5") (pintype "passive"))
    )
    (net (code "27") (name "/SDA") (class "Default")
      (node (ref "R58") (pin "1") (pinfunction "1_1") (pintype "passive"))
      (node (ref "TP2") (pin "1") (pinfunction "1_1") (pintype "passive"))
      (node (ref "U1") (pin "4") (pinfunction "SDA_4") (pintype "passive"))
    )
    (net (code "28") (name "/SNSN") (class "Default")
      (node (ref "R57") (pin "1") (pinfunction "1_1") (pintype "passive"))
    )
    (net (code "29") (name "/SNSP") (class "Default")
      (node (ref "R56") (pin "1") (pinfunction "1_1") (pintype "passive"))
    )
    (net (code "30") (name "/SRN") (class "Default")
      (node (ref "C20") (pin "2") (pinfunction "2_2") (pintype "passive"))
      (node (ref "C22") (pin "1") (pinfunction "1_1") (pintype "passive"))
      (node (ref "R57") (pin "2") (pinfunction "2_2") (pintype "passive"))
      (node (ref "TP1") (pin "1") (pinfunction "1_1") (pintype "passive"))
      (node (ref "U1") (pin "43") (pinfunction "SRN_43") (pintype "passive"))
    )
    (net (code "31") (name "/SRP") (class "Default")
      (node (ref "C19") (pin "2") (pinfunction "2_2") (pintype "passive"))
      (node (ref "C20") (pin "1") (pinfunction "1_1") (pintype "passive"))
      (node (ref "R56") (pin "2") (pinfunction "2_2") (pintype "passive"))
      (node (ref "TP1") (pin "2") (pinfunction "2_2") (pintype "passive"))
      (node (ref "U1") (pin "42") (pinfunction "SRP_42") (pintype "passive"))
    )
    (net (code "32") (name "/TS1") (class "Default")
      (node (ref "C25") (pin "2") (pinfunction "2_2") (pintype "passive"))
      (node (ref "D20") (pin "1") (pinfunction "1_1") (pintype "passive"))
      (node (ref "RT3") (pin "2") (pinfunction "2_2") (pintype "passive"))
      (node (ref "TP15") (pin "1") (pinfunction "1_1") (pintype "passive"))
      (node (ref "U1") (pin "6") (pinfunction "TS1_6") (pintype "passive"))
    )
    (net (code "33") (name "/TS2") (class "Default")
      (node (ref "C24") (pin "1") (pinfunction "1_1") (pintype "passive"))
      (node (ref "RT2") (pin "2") (pinfunction "2_2") (pintype "passive"))
      (node (ref "TP13") (pin "1") (pinfunction "1_1") (pintype "passive"))
      (node (ref "U1") (pin "13") (pinfunction "TS2_13") (pintype "passive"))
    )
    (net (code "34") (name "/TS3") (class "Default")
      (node (ref "C23") (pin "1") (pinfunction "1_1") (pintype "passive"))
      (node (ref "RT1") (pin "2") (pinfunction "2_2") (pintype "passive"))
      (node (ref "TP11") (pin "1") (pinfunction "1_1") (pintype "passive"))
      (node (ref "U1") (pin "18") (pinfunction "TS3_18") (pintype "passive"))
    )
    (net (code "35") (name "/VC5x") (class "Default")
      (node (ref "C10") (pin "1") (pinfunction "1_1") (pintype "passive"))
      (node (ref "C18") (pin "1") (pinfunction "1_1") (pintype "passive"))
      (node (ref "C24") (pin "2") (pinfunction "2_2") (pintype "passive"))
      (node (ref "C27") (pin "2") (pinfunction "2_2") (pintype "passive"))
      (node (ref "C31") (pin "1") (pinfunction "1_1") (pintype "passive"))
      (node (ref "C32") (pin "2") (pinfunction "2_2") (pintype "passive"))
      (node (ref "D18") (pin "1") (pinfunction "1_1") (pintype "passive"))
      (node (ref "R40") (pin "2") (pinfunction "2_2") (pintype "passive"))
      (node (ref "R59") (pin "1") (pinfunction "1_1") (pintype "passive"))
      (node (ref "RT2") (pin "1") (pinfunction "1_1") (pintype "passive"))
      (node (ref "TP14") (pin "1") (pinfunction "1_1") (pintype "passive"))
      (node (ref "U1") (pin "10") (pinfunction "VC5x_10") (pintype "passive"))
    )
    (net (code "36") (name "/VC10x") (class "Default")
      (node (ref "C17") (pin "1") (pinfunction "1_1") (pintype "passive"))
      (node (ref "C23") (pin "2") (pinfunction "2_2") (pintype "passive"))
      (node (ref "C26") (pin "2") (pinfunction "2_2") (pintype "passive"))
      (node (ref "C30") (pin "1") (pinfunction "1_1") (pintype "passive"))
      (node (ref "C31") (pin "2") (pinfunction "2_2") (pintype "passive"))
      (node (ref "C5") (pin "1") (pinfunction "1_1") (pintype "passive"))
      (node (ref "D17") (pin "1") (pinfunction "1_1") (pintype "passive"))
      (node (ref "R28") (pin "2") (pinfunction "2_2") (pintype "passive"))
      (node (ref "RT1") (pin "1") (pinfunction "1_1") (pintype "passive"))
      (node (ref "TP12") (pin "1") (pinfunction "1_1") (pintype "passive"))
      (node (ref "U1") (pin "15") (pinfunction "VC10x_15") (pintype "passive"))
    )
    (net (code "37") (name "/VC15x") (class "Default")
      (node (ref "C30") (pin "2") (pinfunction "2_2") (pintype "passive"))
      (node (ref "D16") (pin "1") (pinfunction "1_1") (pintype "passive"))
      (node (ref "R16") (pin "2") (pinfunction "2_2") (pintype "passive"))
      (node (ref "TP10") (pin "1") (pinfunction "1_1") (pintype "passive"))
      (node (ref "U1") (pin "20") (pinfunction "BAT_20") (pintype "passive"))
    )
    (net (code "38") (name "/WAKE") (class "Default")
      (node (ref "R68") (pin "2") (pinfunction "2_2") (pintype "passive"))
    )
    (net (code "39") (name "GND") (class "Default")
      (node (ref "C16") (pin "1") (pinfunction "1_1") (pintype "passive"))
      (node (ref "C19") (pin "1") (pinfunction "1_1") (pintype "passive"))
      (node (ref "C21") (pin "1") (pinfunction "1_1") (pintype "passive"))
      (node (ref "C22") (pin "2") (pinfunction "2_2") (pintype "passive"))
      (node (ref "C25") (pin "1") (pinfunction "1_1") (pintype "passive"))
      (node (ref "C28") (pin "1") (pinfunction "1_1") (pintype "passive"))
      (node (ref "C29") (pin "1") (pinfunction "1_1") (pintype "passive"))
      (node (ref "C32") (pin "1") (pinfunction "1_1") (pintype "passive"))
      (node (ref "C33") (pin "1") (pinfunction "1_1") (pintype "passive"))
      (node (ref "C34") (pin "1") (pinfunction "1_1") (pintype "passive"))
      (node (ref "C35") (pin "1") (pinfunction "1_1") (pintype "passive"))
      (node (ref "D21") (pin "2") (pinfunction "2_2") (pintype "passive"))
      (node (ref "D22") (pin "2") (pinfunction "2_2") (pintype "passive"))
      (node (ref "Q20") (pin "2") (pinfunction "S_2") (pintype "passive"))
      (node (ref "R55") (pin "1") (pinfunction "1_1") (pintype "passive"))
      (node (ref "R69") (pin "1") (pinfunction "1_1") (pintype "passive"))
      (node (ref "RT3") (pin "1") (pinfunction "1_1") (pintype "passive"))
      (node (ref "TP4") (pin "1") (pinfunction "1_1") (pintype "passive"))
      (node (ref "TP5") (pin "1") (pinfunction "1_1") (pintype "passive"))
      (node (ref "TP6") (pin "1") (pinfunction "1_1") (pintype "passive"))
      (node (ref "TP7") (pin "1") (pinfunction "1_1") (pintype "passive"))
      (node (ref "U1") (pin "3") (pinfunction "VSS_3") (pintype "passive"))
    )
    (net (code "40") (name "Net-(D19-Pad1)") (class "Default")
      (node (ref "D19") (pin "1") (pinfunction "1_1") (pintype "passive"))
      (node (ref "R61") (pin "1") (pinfunction "1_1") (pintype "passive"))
      (node (ref "R62") (pin "2") (pinfunction "2_2") (pintype "passive"))
    )
    (net (code "41") (name "Net-(D20-Pad2)") (class "Default")
      (node (ref "D20") (pin "2") (pinfunction "2_2") (pintype "passive"))
      (node (ref "D21") (pin "1") (pinfunction "1_1") (pintype "passive"))
      (node (ref "R64") (pin "1") (pinfunction "1_1") (pintype "passive"))
      (node (ref "R66") (pin "1") (pinfunction "1_1") (pintype "passive"))
    )
    (net (code "42") (name "Net-(D22-Pad1)") (class "Default")
      (node (ref "D22") (pin "1") (pinfunction "1_1") (pintype "passive"))
      (node (ref "R66") (pin "2") (pinfunction "2_2") (pintype "passive"))
      (node (ref "R68") (pin "1") (pinfunction "1_1") (pintype "passive"))
    )
    (net (code "43") (name "Net-(Q1-D)") (class "Default")
      (node (ref "Q1") (pin "3") (pinfunction "D_3") (pintype "passive"))
      (node (ref "R7") (pin "2") (pinfunction "2_2") (pintype "passive"))
    )
    (net (code "44") (name "Net-(Q1-G)") (class "Default")
      (node (ref "D2") (pin "1") (pinfunction "1_1") (pintype "passive"))
      (node (ref "Q1") (pin "1") (pinfunction "G_1") (pintype "passive"))
      (node (ref "R18") (pin "1") (pinfunction "1_1") (pintype "passive"))
    )
    (net (code "45") (name "Net-(Q2-D)") (class "Default")
      (node (ref "Q2") (pin "3") (pinfunction "D_3") (pintype "passive"))
      (node (ref "R8") (pin "2") (pinfunction "2_2") (pintype "passive"))
    )
    (net (code "46") (name "Net-(Q2-G)") (class "Default")
      (node (ref "D3") (pin "1") (pinfunction "1_1") (pintype "passive"))
      (node (ref "Q2") (pin "1") (pinfunction "G_1") (pintype "passive"))
      (node (ref "R20") (pin "1") (pinfunction "1_1") (pintype "passive"))
    )
    (net (code "47") (name "Net-(Q3-D)") (class "Default")
      (node (ref "Q3") (pin "3") (pinfunction "D_3") (pintype "passive"))
      (node (ref "R9") (pin "2") (pinfunction "2_2") (pintype "passive"))
    )
    (net (code "48") (name "Net-(Q3-G)") (class "Default")
      (node (ref "D4") (pin "1") (pinfunction "1_1") (pintype "passive"))
      (node (ref "Q3") (pin "1") (pinfunction "G_1") (pintype "passive"))
      (node (ref "R22") (pin "1") (pinfunction "1_1") (pintype "passive"))
    )
    (net (code "49") (name "Net-(Q4-D)") (class "Default")
      (node (ref "Q4") (pin "3") (pinfunction "D_3") (pintype "passive"))
      (node (ref "R10") (pin "2") (pinfunction "2_2") (pintype "passive"))
    )
    (net (code "50") (name "Net-(Q4-G)") (class "Default")
      (node (ref "D5") (pin "1") (pinfunction "1_1") (pintype "passive"))
      (node (ref "Q4") (pin "1") (pinfunction "G_1") (pintype "passive"))
      (node (ref "R24") (pin "1") (pinfunction "1_1") (pintype "passive"))
    )
    (net (code "51") (name "Net-(Q5-D)") (class "Default")
      (node (ref "Q5") (pin "3") (pinfunction "D_3") (pintype "passive"))
      (node (ref "R11") (pin "2") (pinfunction "2_2") (pintype "passive"))
    )
    (net (code "52") (name "Net-(Q5-G)") (class "Default")
      (node (ref "D15") (pin "1") (pinfunction "1_1") (pintype "passive"))
      (node (ref "Q5") (pin "1") (pinfunction "G_1") (pintype "passive"))
      (node (ref "R26") (pin "1") (pinfunction "1_1") (pintype "passive"))
    )
    (net (code "53") (name "Net-(Q6-D)") (class "Default")
      (node (ref "Q6") (pin "3") (pinfunction "D_3") (pintype "passive"))
      (node (ref "R12") (pin "2") (pinfunction "2_2") (pintype "passive"))
    )
    (net (code "54") (name "Net-(Q6-G)") (class "Default")
      (node (ref "D6") (pin "1") (pinfunction "1_1") (pintype "passive"))
      (node (ref "Q6") (pin "1") (pinfunction "G_1") (pintype "passive"))
      (node (ref "R30") (pin "1") (pinfunction "1_1") (pintype "passive"))
    )
    (net (code "55") (name "Net-(Q7-D)") (class "Default")
      (node (ref "Q7") (pin "3") (pinfunction "D_3") (pintype "passive"))
      (node (ref "R13") (pin "2") (pinfunction "2_2") (pintype "passive"))
    )
    (net (code "56") (name "Net-(Q7-G)") (class "Default")
      (node (ref "D7") (pin "1") (pinfunction "1_1") (pintype "passive"))
      (node (ref "Q7") (pin "1") (pinfunction "G_1") (pintype "passive"))
      (node (ref "R32") (pin "1") (pinfunction "1_1") (pintype "passive"))
    )
    (net (code "57") (name "Net-(Q8-D)") (class "Default")
      (node (ref "Q8") (pin "3") (pinfunction "D_3") (pintype "passive"))
      (node (ref "R14") (pin "2") (pinfunction "2_2") (pintype "passive"))
    )
    (net (code "58") (name "Net-(Q8-G)") (class "Default")
      (node (ref "D8") (pin "1") (pinfunction "1_1") (pintype "passive"))
      (node (ref "Q8") (pin "1") (pinfunction "G_1") (pintype "passive"))
      (node (ref "R34") (pin "1") (pinfunction "1_1") (pintype "passive"))
    )
    (net (code "59") (name "Net-(Q9-D)") (class "Default")
      (node (ref "Q9") (pin "3") (pinfunction "D_3") (pintype "passive"))
      (node (ref "R15") (pin "2") (pinfunction "2_2") (pintype "passive"))
    )
    (net (code "60") (name "Net-(Q9-G)") (class "Default")
      (node (ref "D9") (pin "1") (pinfunction "1_1") (pintype "passive"))
      (node (ref "Q9") (pin "1") (pinfunction "G_1") (pintype "passive"))
      (node (ref "R36") (pin "1") (pinfunction "1_1") (pintype "passive"))
    )
    (net (code "61") (name "Net-(Q10-D)") (class "Default")
      (node (ref "Q10") (pin "3") (pinfunction "D_3") (pintype "passive"))
      (node (ref "R2") (pin "2") (pinfunction "2_2") (pintype "passive"))
    )
    (net (code "62") (name "Net-(Q10-G)") (class "Default")
      (node (ref "D1") (pin "1") (pinfunction "1_1") (pintype "passive"))
      (node (ref "Q10") (pin "1") (pinfunction "G_1") (pintype "passive"))
      (node (ref "R38") (pin "1") (pinfunction "1_1") (pintype "passive"))
    )
    (net (code "63") (name "Net-(Q11-D)") (class "Default")
      (node (ref "Q11") (pin "3") (pinfunction "D_3") (pintype "passive"))
      (node (ref "R3") (pin "2") (pinfunction "2_2") (pintype "passive"))
    )
    (net (code "64") (name "Net-(Q11-G)") (class "Default")
      (node (ref "D10") (pin "1") (pinfunction "1_1") (pintype "passive"))
      (node (ref "Q11") (pin "1") (pinfunction "G_1") (pintype "passive"))
      (node (ref "R42") (pin "1") (pinfunction "1_1") (pintype "passive"))
    )
    (net (code "65") (name "Net-(Q12-D)") (class "Default")
      (node (ref "Q12") (pin "3") (pinfunction "D_3") (pintype "passive"))
      (node (ref "R1") (pin "2") (pinfunction "2_2") (pintype "passive"))
    )
    (net (code "66") (name "Net-(Q12-G)") (class "Default")
      (node (ref "D11") (pin "1") (pinfunction "1_1") (pintype "passive"))
      (node (ref "Q12") (pin "1") (pinfunction "G_1") (pintype "passive"))
      (node (ref "R44") (pin "1") (pinfunction "1_1") (pintype "passive"))
    )
    (net (code "67") (name "Net-(Q13-D)") (class "Default")
      (node (ref "Q13") (pin "3") (pinfunction "D_3") (pintype "passive"))
      (node (ref "R4") (pin "2") (pinfunction "2_2") (pintype "passive"))
    )
    (net (code "68") (name "Net-(Q13-G)") (class "Default")
      (node (ref "D12") (pin "1") (pinfunction "1_1") (pintype "passive"))
      (node (ref "Q13") (pin "1") (pinfunction "G_1") (pintype "passive"))
      (node (ref "R46") (pin "1") (pinfunction "1_1") (pintype "passive"))
    )
    (net (code "69") (name "Net-(Q14-D)") (class "Default")
      (node (ref "Q14") (pin "3") (pinfunction "D_3") (pintype "passive"))
      (node (ref "R5") (pin "2") (pinfunction "2_2") (pintype "passive"))
    )
    (net (code "70") (name "Net-(Q14-G)") (class "Default")
      (node (ref "D13") (pin "1") (pinfunction "1_1") (pintype "passive"))
      (node (ref "Q14") (pin "1") (pinfunction "G_1") (pintype "passive"))
      (node (ref "R48") (pin "1") (pinfunction "1_1") (pintype "passive"))
    )
    (net (code "71") (name "Net-(Q15-D)") (class "Default")
      (node (ref "Q15") (pin "3") (pinfunction "D_3") (pintype "passive"))
      (node (ref "R6") (pin "2") (pinfunction "2_2") (pintype "passive"))
    )
    (net (code "72") (name "Net-(Q15-G)") (class "Default")
      (node (ref "D14") (pin "1") (pinfunction "1_1") (pintype "passive"))
      (node (ref "Q15") (pin "1") (pinfunction "G_1") (pintype "passive"))
      (node (ref "R50") (pin "1") (pinfunction "1_1") (pintype "passive"))
    )
    (net (code "73") (name "Net-(Q16-D)") (class "Default")
      (node (ref "C34") (pin "2") (pinfunction "2_2") (pintype "passive"))
      (node (ref "Q16") (pin "3") (pinfunction "D_3") (pintype "passive"))
      (node (ref "R62") (pin "1") (pinfunction "1_1") (pintype "passive"))
    )
    (net (code "74") (name "Net-(Q16-G)") (class "Default")
      (node (ref "Q16") (pin "1") (pinfunction "G_1") (pintype "passive"))
      (node (ref "R59") (pin "2") (pinfunction "2_2") (pintype "passive"))
    )
    (net (code "75") (name "Net-(Q17-C-Pad2)") (class "Default")
      (node (ref "Q17") (pin "2") (pinfunction "C_2") (pintype "passive"))
      (node (ref "Q17") (pin "4") (pinfunction "C_4") (pintype "passive"))
      (node (ref "R63") (pin "1") (pinfunction "1_1") (pintype "passive"))
    )
    (net (code "76") (name "Net-(Q18-D)") (class "Default")
      (node (ref "Q18") (pin "3") (pinfunction "D_3") (pintype "passive"))
      (node (ref "Q19") (pin "3") (pinfunction "D_3") (pintype "passive"))
      (node (ref "R70") (pin "2") (pinfunction "2_2") (pintype "passive"))
    )
    (net (code "77") (name "Net-(Q18-G)") (class "Default")
      (node (ref "Q18") (pin "1") (pinfunction "G_1") (pintype "passive"))
      (node (ref "Q20") (pin "3") (pinfunction "D_3") (pintype "passive"))
      (node (ref "R69") (pin "2") (pinfunction "2_2") (pintype "passive"))
      (node (ref "R70") (pin "1") (pinfunction "1_1") (pintype "passive"))
    )
    (net (code "78") (name "Net-(Q18-S)") (class "Default")
      (node (ref "Q18") (pin "2") (pinfunction "S_2") (pintype "passive"))
      (node (ref "R64") (pin "2") (pinfunction "2_2") (pintype "passive"))
    )
    (net (code "79") (name "Net-(Q19-G)") (class "Default")
      (node (ref "C36") (pin "2") (pinfunction "2_2") (pintype "passive"))
      (node (ref "D23") (pin "2") (pinfunction "2_2") (pintype "passive"))
      (node (ref "Q19") (pin "1") (pinfunction "G_1") (pintype "passive"))
      (node (ref "R65") (pin "1") (pinfunction "1_1") (pintype "passive"))
    )
    (net (code "80") (name "Net-(Q20-G)") (class "Default")
      (node (ref "Q20") (pin "1") (pinfunction "G_1") (pintype "passive"))
      (node (ref "R67") (pin "2") (pinfunction "2_2") (pintype "passive"))
    )
    (net (code "81") (name "Net-(U1-VC0)") (class "Default")
      (node (ref "C15") (pin "1") (pinfunction "1_1") (pintype "passive"))
      (node (ref "C16") (pin "2") (pinfunction "2_2") (pintype "passive"))
      (node (ref "R50") (pin "2") (pinfunction "2_2") (pintype "passive"))
      (node (ref "R51") (pin "2") (pinfunction "2_2") (pintype "passive"))
      (node (ref "U1") (pin "41") (pinfunction "VC0_41") (pintype "passive"))
    )
    (net (code "82") (name "Net-(U1-VC1)") (class "Default")
      (node (ref "C14") (pin "1") (pinfunction "1_1") (pintype "passive"))
      (node (ref "C15") (pin "2") (pinfunction "2_2") (pintype "passive"))
      (node (ref "R48") (pin "2") (pinfunction "2_2") (pintype "passive"))
      (node (ref "R49") (pin "2") (pinfunction "2_2") (pintype "passive"))
      (node (ref "U1") (pin "40") (pinfunction "VC1_40") (pintype "passive"))
    )
    (net (code "83") (name "Net-(U1-VC2)") (class "Default")
      (node (ref "C13") (pin "1") (pinfunction "1_1") (pintype "passive"))
      (node (ref "C14") (pin "2") (pinfunction "2_2") (pintype "passive"))
      (node (ref "R46") (pin "2") (pinfunction "2_2") (pintype "passive"))
      (node (ref "R47") (pin "2") (pinfunction "2_2") (pintype "passive"))
      (node (ref "U1") (pin "39") (pinfunction "VC2_39") (pintype "passive"))
    )
    (net (code "84") (name "Net-(U1-VC3)") (class "Default")
      (node (ref "C12") (pin "1") (pinfunction "1_1") (pintype "passive"))
      (node (ref "C13") (pin "2") (pinfunction "2_2") (pintype "passive"))
      (node (ref "R44") (pin "2") (pinfunction "2_2") (pintype "passive"))
      (node (ref "R45") (pin "2") (pinfunction "2_2") (pintype "passive"))
      (node (ref "R54") (pin "1") (pinfunction "1_1") (pintype "passive"))
      (node (ref "U1") (pin "38") (pinfunction "VC3_38") (pintype "passive"))
    )
    (net (code "85") (name "Net-(U1-VC4)") (class "Default")
      (node (ref "C11") (pin "1") (pinfunction "1_1") (pintype "passive"))
      (node (ref "C12") (pin "2") (pinfunction "2_2") (pintype "passive"))
      (node (ref "R42") (pin "2") (pinfunction "2_2") (pintype "passive"))
      (node (ref "R43") (pin "2") (pinfunction "2_2") (pintype "passive"))
      (node (ref "R54") (pin "2") (pinfunction "2_2") (pintype "passive"))
      (node (ref "U1") (pin "37") (pinfunction "VC4_37") (pintype "passive"))
    )
    (net (code "86") (name "Net-(U1-VC5)") (class "Default")
      (node (ref "C11") (pin "2") (pinfunction "2_2") (pintype "passive"))
      (node (ref "D18") (pin "2") (pinfunction "2_2") (pintype "passive"))
      (node (ref "R41") (pin "2") (pinfunction "2_2") (pintype "passive"))
      (node (ref "U1") (pin "36") (pinfunction "VC5_36") (pintype "passive"))
    )
    (net (code "87") (name "Net-(U1-VC5B)") (class "Default")
      (node (ref "C18") (pin "2") (pinfunction "2_2") (pintype "passive"))
      (node (ref "R38") (pin "2") (pinfunction "2_2") (pintype "passive"))
      (node (ref "R39") (pin "2") (pinfunction "2_2") (pintype "passive"))
      (node (ref "U1") (pin "35") (pinfunction "VC5B_35") (pintype "passive"))
    )
    (net (code "88") (name "Net-(U1-VC6)") (class "Default")
      (node (ref "C10") (pin "2") (pinfunction "2_2") (pintype "passive"))
      (node (ref "C9") (pin "1") (pinfunction "1_1") (pintype "passive"))
      (node (ref "R36") (pin "2") (pinfunction "2_2") (pintype "passive"))
      (node (ref "R37") (pin "2") (pinfunction "2_2") (pintype "passive"))
      (node (ref "U1") (pin "34") (pinfunction "VC6_34") (pintype "passive"))
    )
    (net (code "89") (name "Net-(U1-VC7)") (class "Default")
      (node (ref "C8") (pin "1") (pinfunction "1_1") (pintype "passive"))
      (node (ref "C9") (pin "2") (pinfunction "2_2") (pintype "passive"))
      (node (ref "R34") (pin "2") (pinfunction "2_2") (pintype "passive"))
      (node (ref "R35") (pin "2") (pinfunction "2_2") (pintype "passive"))
      (node (ref "U1") (pin "33") (pinfunction "VC7_33") (pintype "passive"))
    )
    (net (code "90") (name "Net-(U1-VC8)") (class "Default")
      (node (ref "C7") (pin "1") (pinfunction "1_1") (pintype "passive"))
      (node (ref "C8") (pin "2") (pinfunction "2_2") (pintype "passive"))
      (node (ref "R32") (pin "2") (pinfunction "2_2") (pintype "passive"))
      (node (ref "R33") (pin "2") (pinfunction "2_2") (pintype "passive"))
      (node (ref "R53") (pin "1") (pinfunction "1_1") (pintype "passive"))
      (node (ref "U1") (pin "32") (pinfunction "VC8_32") (pintype "passive"))
    )
    (net (code "91") (name "Net-(U1-VC9)") (class "Default")
      (node (ref "C6") (pin "1") (pinfunction "1_1") (pintype "passive"))
      (node (ref "C7") (pin "2") (pinfunction "2_2") (pintype "passive"))
      (node (ref "R30") (pin "2") (pinfunction "2_2") (pintype "passive"))
      (node (ref "R31") (pin "2") (pinfunction "2_2") (pintype "passive"))
      (node (ref "R53") (pin "2") (pinfunction "2_2") (pintype "passive"))
      (node (ref "U1") (pin "31") (pinfunction "VC9_31") (pintype "passive"))
    )
    (net (code "92") (name "Net-(U1-VC10)") (class "Default")
      (node (ref "C6") (pin "2") (pinfunction "2_2") (pintype "passive"))
      (node (ref "D17") (pin "2") (pinfunction "2_2") (pintype "passive"))
      (node (ref "R29") (pin "2") (pinfunction "2_2") (pintype "passive"))
      (node (ref "U1") (pin "30") (pinfunction "VC10_30") (pintype "passive"))
    )
    (net (code "93") (name "Net-(U1-VC10B)") (class "Default")
      (node (ref "C17") (pin "2") (pinfunction "2_2") (pintype "passive"))
      (node (ref "R26") (pin "2") (pinfunction "2_2") (pintype "passive"))
      (node (ref "R27") (pin "2") (pinfunction "2_2") (pintype "passive"))
      (node (ref "U1") (pin "29") (pinfunction "VC10B_29") (pintype "passive"))
    )
    (net (code "94") (name "Net-(U1-VC11)") (class "Default")
      (node (ref "C4") (pin "1") (pinfunction "1_1") (pintype "passive"))
      (node (ref "C5") (pin "2") (pinfunction "2_2") (pintype "passive"))
      (node (ref "R24") (pin "2") (pinfunction "2_2") (pintype "passive"))
      (node (ref "R25") (pin "2") (pinfunction "2_2") (pintype "passive"))
      (node (ref "U1") (pin "28") (pinfunction "VC11_28") (pintype "passive"))
    )
    (net (code "95") (name "Net-(U1-VC12)") (class "Default")
      (node (ref "C3") (pin "1") (pinfunction "1_1") (pintype "passive"))
      (node (ref "C4") (pin "2") (pinfunction "2_2") (pintype "passive"))
      (node (ref "R22") (pin "2") (pinfunction "2_2") (pintype "passive"))
      (node (ref "R23") (pin "2") (pinfunction "2_2") (pintype "passive"))
      (node (ref "U1") (pin "27") (pinfunction "VC12_27") (pintype "passive"))
    )
    (net (code "96") (name "Net-(U1-VC13)") (class "Default")
      (node (ref "C2") (pin "1") (pinfunction "1_1") (pintype "passive"))
      (node (ref "C3") (pin "2") (pinfunction "2_2") (pintype "passive"))
      (node (ref "R20") (pin "2") (pinfunction "2_2") (pintype "passive"))
      (node (ref "R21") (pin "2") (pinfunction "2_2") (pintype "passive"))
      (node (ref "R52") (pin "1") (pinfunction "1_1") (pintype "passive"))
      (node (ref "U1") (pin "26") (pinfunction "VC13_26") (pintype "passive"))
    )
    (net (code "97") (name "Net-(U1-VC14)") (class "Default")
      (node (ref "C1") (pin "1") (pinfunction "1_1") (pintype "passive"))
      (node (ref "C2") (pin "2") (pinfunction "2_2") (pintype "passive"))
      (node (ref "R18") (pin "2") (pinfunction "2_2") (pintype "passive"))
      (node (ref "R19") (pin "2") (pinfunction "2_2") (pintype "passive"))
      (node (ref "R52") (pin "2") (pinfunction "2_2") (pintype "passive"))
      (node (ref "U1") (pin "25") (pinfunction "VC14_25") (pintype "passive"))
    )
    (net (code "98") (name "Net-(U1-VC15)") (class "Default")
      (node (ref "C1") (pin "2") (pinfunction "2_2") (pintype "passive"))
      (node (ref "D16") (pin "2") (pinfunction "2_2") (pintype "passive"))
      (node (ref "R17") (pin "2") (pinfunction "2_2") (pintype "passive"))
      (node (ref "U1") (pin "24") (pinfunction "VC15_24") (pintype "passive"))
    )
    (net (code "99") (name "REGOUT") (class "Default")
      (node (ref "C29") (pin "2") (pinfunction "2_2") (pintype "passive"))
      (node (ref "NT1") (pin "1") (pinfunction "1_1") (pintype "passive"))
      (node (ref "R58") (pin "2") (pinfunction "2_2") (pintype "passive"))
      (node (ref "R60") (pin "2") (pinfunction "2_2") (pintype "passive"))
      (node (ref "R67") (pin "1") (pinfunction "1_1") (pintype "passive"))
      (node (ref "U1") (pin "8") (pinfunction "REGOUT_8") (pintype "passive"))
    )
    (net (code "100") (name "VCC") (class "Default")
      (node (ref "NT1") (pin "2") (pinfunction "2_2") (pintype "passive"))
      (node (ref "TP8") (pin "1") (pinfunction "1_1") (pintype "passive"))
    )
    (net (code "101") (name "unconnected-(U1-NC-Pad21)") (class "Default")
      (node (ref "U1") (pin "21") (pinfunction "NC_21") (pintype "passive"))
    )
    (net (code "102") (name "unconnected-(U1-NC-Pad22)") (class "Default")
      (node (ref "U1") (pin "22") (pinfunction "NC_22") (pintype "passive"))
    )
    (net (code "103") (name "unconnected-(U1-NC-Pad23)") (class "Default")
      (node (ref "U1") (pin "23") (pinfunction "NC_23") (pintype "passive"))
    )
  )
)
